# LED.net
KiCad netlist of a schematic drawn in Altium Designer
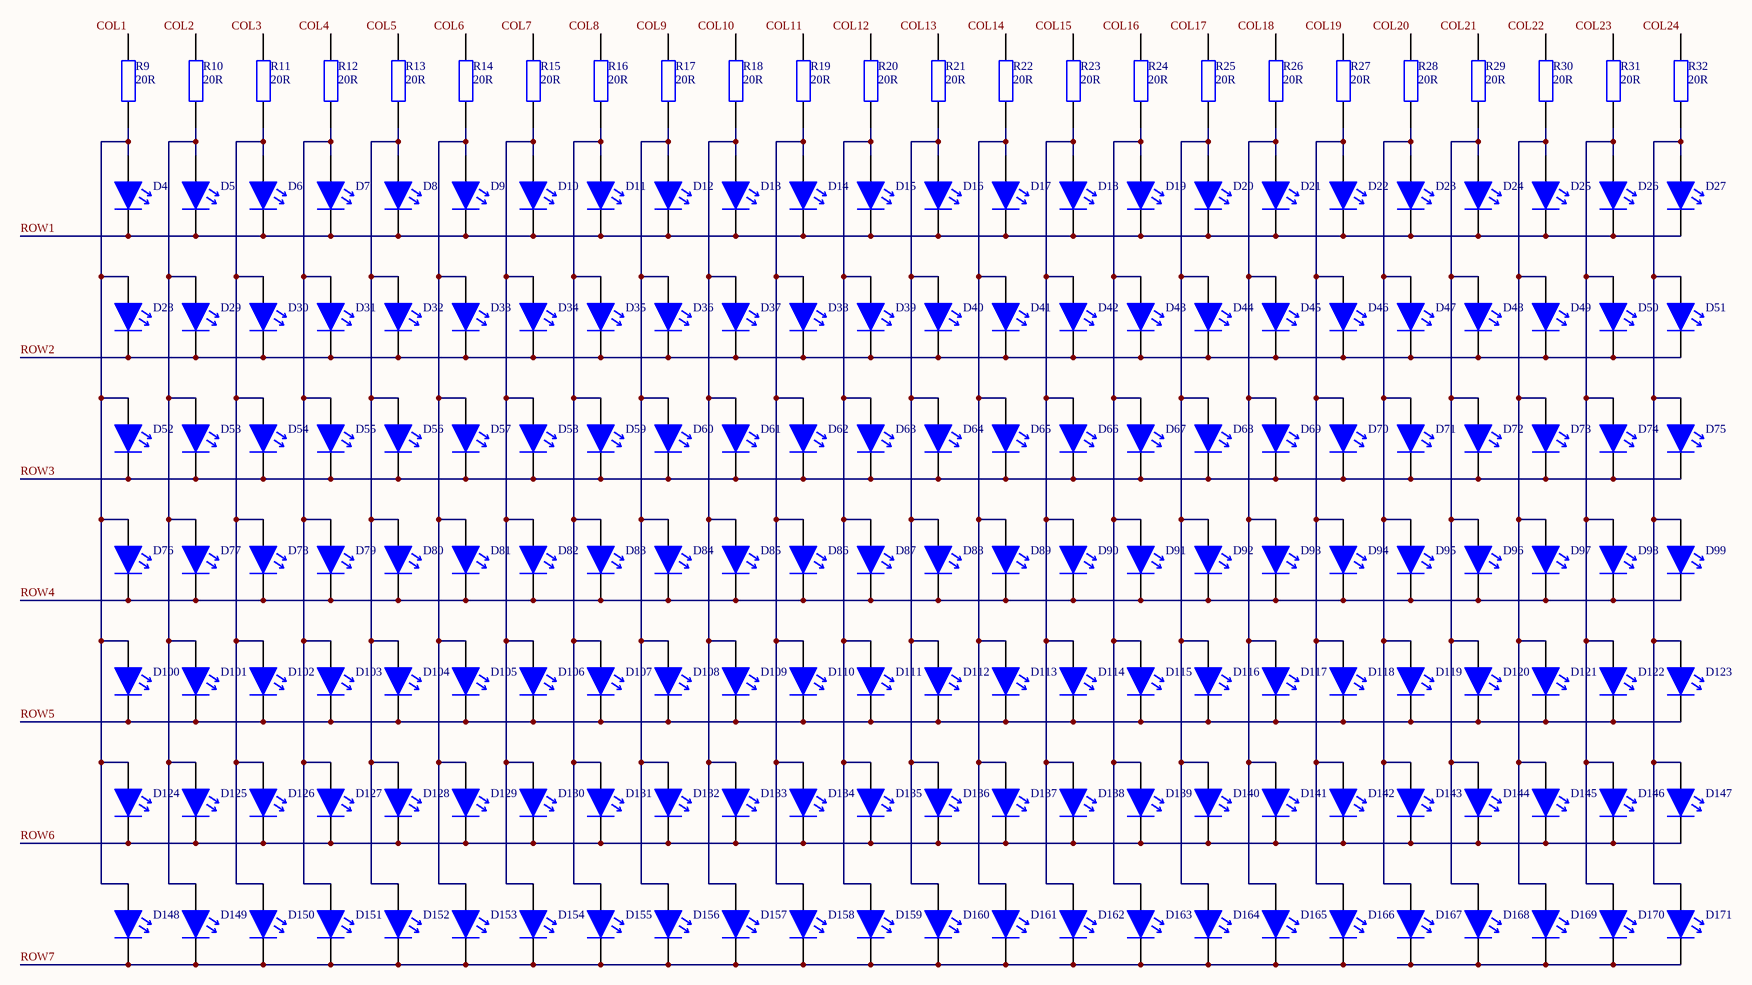
[diagram p0: LED.SchDoc]

(export (version "E")
  (design (tool "Eeschema 10.0.6"))
  (components
    (comp (ref "D4")
      (value "EAHE2835WD63")
      (footprint "LED_WHITE_1411_PLCC2")
      (description "LED Uni-Color White 39lm 6500K Chip LED 2-Pin PLCC T/R")
      (fields (field (name "MANUFACTURER") "Everlight") (field (name "DESIGNEDBY") "Aslı Kurt"))
      (libsource (lib "MyLibrary") (part "LED COOL WHITE 6500K 2PLCC 1411"))
    )
    (comp (ref "D5")
      (value "EAHE2835WD63")
      (footprint "LED_WHITE_1411_PLCC2")
      (description "LED Uni-Color White 39lm 6500K Chip LED 2-Pin PLCC T/R")
      (fields (field (name "MANUFACTURER") "Everlight") (field (name "DESIGNEDBY") "Aslı Kurt"))
      (libsource (lib "MyLibrary") (part "LED COOL WHITE 6500K 2PLCC 1411"))
    )
    (comp (ref "D6")
      (value "EAHE2835WD63")
      (footprint "LED_WHITE_1411_PLCC2")
      (description "LED Uni-Color White 39lm 6500K Chip LED 2-Pin PLCC T/R")
      (fields (field (name "MANUFACTURER") "Everlight") (field (name "DESIGNEDBY") "Aslı Kurt"))
      (libsource (lib "MyLibrary") (part "LED COOL WHITE 6500K 2PLCC 1411"))
    )
    (comp (ref "D7")
      (value "EAHE2835WD63")
      (footprint "LED_WHITE_1411_PLCC2")
      (description "LED Uni-Color White 39lm 6500K Chip LED 2-Pin PLCC T/R")
      (fields (field (name "MANUFACTURER") "Everlight") (field (name "DESIGNEDBY") "Aslı Kurt"))
      (libsource (lib "MyLibrary") (part "LED COOL WHITE 6500K 2PLCC 1411"))
    )
    (comp (ref "D8")
      (value "EAHE2835WD63")
      (footprint "LED_WHITE_1411_PLCC2")
      (description "LED Uni-Color White 39lm 6500K Chip LED 2-Pin PLCC T/R")
      (fields (field (name "MANUFACTURER") "Everlight") (field (name "DESIGNEDBY") "Aslı Kurt"))
      (libsource (lib "MyLibrary") (part "LED COOL WHITE 6500K 2PLCC 1411"))
    )
    (comp (ref "D9")
      (value "EAHE2835WD63")
      (footprint "LED_WHITE_1411_PLCC2")
      (description "LED Uni-Color White 39lm 6500K Chip LED 2-Pin PLCC T/R")
      (fields (field (name "MANUFACTURER") "Everlight") (field (name "DESIGNEDBY") "Aslı Kurt"))
      (libsource (lib "MyLibrary") (part "LED COOL WHITE 6500K 2PLCC 1411"))
    )
    (comp (ref "D10")
      (value "EAHE2835WD63")
      (footprint "LED_WHITE_1411_PLCC2")
      (description "LED Uni-Color White 39lm 6500K Chip LED 2-Pin PLCC T/R")
      (fields (field (name "MANUFACTURER") "Everlight") (field (name "DESIGNEDBY") "Aslı Kurt"))
      (libsource (lib "MyLibrary") (part "LED COOL WHITE 6500K 2PLCC 1411"))
    )
    (comp (ref "D11")
      (value "EAHE2835WD63")
      (footprint "LED_WHITE_1411_PLCC2")
      (description "LED Uni-Color White 39lm 6500K Chip LED 2-Pin PLCC T/R")
      (fields (field (name "MANUFACTURER") "Everlight") (field (name "DESIGNEDBY") "Aslı Kurt"))
      (libsource (lib "MyLibrary") (part "LED COOL WHITE 6500K 2PLCC 1411"))
    )
    (comp (ref "D12")
      (value "EAHE2835WD63")
      (footprint "LED_WHITE_1411_PLCC2")
      (description "LED Uni-Color White 39lm 6500K Chip LED 2-Pin PLCC T/R")
      (fields (field (name "MANUFACTURER") "Everlight") (field (name "DESIGNEDBY") "Aslı Kurt"))
      (libsource (lib "MyLibrary") (part "LED COOL WHITE 6500K 2PLCC 1411"))
    )
    (comp (ref "D13")
      (value "EAHE2835WD63")
      (footprint "LED_WHITE_1411_PLCC2")
      (description "LED Uni-Color White 39lm 6500K Chip LED 2-Pin PLCC T/R")
      (fields (field (name "MANUFACTURER") "Everlight") (field (name "DESIGNEDBY") "Aslı Kurt"))
      (libsource (lib "MyLibrary") (part "LED COOL WHITE 6500K 2PLCC 1411"))
    )
    (comp (ref "D14")
      (value "EAHE2835WD63")
      (footprint "LED_WHITE_1411_PLCC2")
      (description "LED Uni-Color White 39lm 6500K Chip LED 2-Pin PLCC T/R")
      (fields (field (name "MANUFACTURER") "Everlight") (field (name "DESIGNEDBY") "Aslı Kurt"))
      (libsource (lib "MyLibrary") (part "LED COOL WHITE 6500K 2PLCC 1411"))
    )
    (comp (ref "D15")
      (value "EAHE2835WD63")
      (footprint "LED_WHITE_1411_PLCC2")
      (description "LED Uni-Color White 39lm 6500K Chip LED 2-Pin PLCC T/R")
      (fields (field (name "MANUFACTURER") "Everlight") (field (name "DESIGNEDBY") "Aslı Kurt"))
      (libsource (lib "MyLibrary") (part "LED COOL WHITE 6500K 2PLCC 1411"))
    )
    (comp (ref "D16")
      (value "EAHE2835WD63")
      (footprint "LED_WHITE_1411_PLCC2")
      (description "LED Uni-Color White 39lm 6500K Chip LED 2-Pin PLCC T/R")
      (fields (field (name "MANUFACTURER") "Everlight") (field (name "DESIGNEDBY") "Aslı Kurt"))
      (libsource (lib "MyLibrary") (part "LED COOL WHITE 6500K 2PLCC 1411"))
    )
    (comp (ref "D17")
      (value "EAHE2835WD63")
      (footprint "LED_WHITE_1411_PLCC2")
      (description "LED Uni-Color White 39lm 6500K Chip LED 2-Pin PLCC T/R")
      (fields (field (name "MANUFACTURER") "Everlight") (field (name "DESIGNEDBY") "Aslı Kurt"))
      (libsource (lib "MyLibrary") (part "LED COOL WHITE 6500K 2PLCC 1411"))
    )
    (comp (ref "D18")
      (value "EAHE2835WD63")
      (footprint "LED_WHITE_1411_PLCC2")
      (description "LED Uni-Color White 39lm 6500K Chip LED 2-Pin PLCC T/R")
      (fields (field (name "MANUFACTURER") "Everlight") (field (name "DESIGNEDBY") "Aslı Kurt"))
      (libsource (lib "MyLibrary") (part "LED COOL WHITE 6500K 2PLCC 1411"))
    )
    (comp (ref "D19")
      (value "EAHE2835WD63")
      (footprint "LED_WHITE_1411_PLCC2")
      (description "LED Uni-Color White 39lm 6500K Chip LED 2-Pin PLCC T/R")
      (fields (field (name "MANUFACTURER") "Everlight") (field (name "DESIGNEDBY") "Aslı Kurt"))
      (libsource (lib "MyLibrary") (part "LED COOL WHITE 6500K 2PLCC 1411"))
    )
    (comp (ref "D20")
      (value "EAHE2835WD63")
      (footprint "LED_WHITE_1411_PLCC2")
      (description "LED Uni-Color White 39lm 6500K Chip LED 2-Pin PLCC T/R")
      (fields (field (name "MANUFACTURER") "Everlight") (field (name "DESIGNEDBY") "Aslı Kurt"))
      (libsource (lib "MyLibrary") (part "LED COOL WHITE 6500K 2PLCC 1411"))
    )
    (comp (ref "D21")
      (value "EAHE2835WD63")
      (footprint "LED_WHITE_1411_PLCC2")
      (description "LED Uni-Color White 39lm 6500K Chip LED 2-Pin PLCC T/R")
      (fields (field (name "MANUFACTURER") "Everlight") (field (name "DESIGNEDBY") "Aslı Kurt"))
      (libsource (lib "MyLibrary") (part "LED COOL WHITE 6500K 2PLCC 1411"))
    )
    (comp (ref "D22")
      (value "EAHE2835WD63")
      (footprint "LED_WHITE_1411_PLCC2")
      (description "LED Uni-Color White 39lm 6500K Chip LED 2-Pin PLCC T/R")
      (fields (field (name "MANUFACTURER") "Everlight") (field (name "DESIGNEDBY") "Aslı Kurt"))
      (libsource (lib "MyLibrary") (part "LED COOL WHITE 6500K 2PLCC 1411"))
    )
    (comp (ref "D23")
      (value "EAHE2835WD63")
      (footprint "LED_WHITE_1411_PLCC2")
      (description "LED Uni-Color White 39lm 6500K Chip LED 2-Pin PLCC T/R")
      (fields (field (name "MANUFACTURER") "Everlight") (field (name "DESIGNEDBY") "Aslı Kurt"))
      (libsource (lib "MyLibrary") (part "LED COOL WHITE 6500K 2PLCC 1411"))
    )
    (comp (ref "D24")
      (value "EAHE2835WD63")
      (footprint "LED_WHITE_1411_PLCC2")
      (description "LED Uni-Color White 39lm 6500K Chip LED 2-Pin PLCC T/R")
      (fields (field (name "MANUFACTURER") "Everlight") (field (name "DESIGNEDBY") "Aslı Kurt"))
      (libsource (lib "MyLibrary") (part "LED COOL WHITE 6500K 2PLCC 1411"))
    )
    (comp (ref "D25")
      (value "EAHE2835WD63")
      (footprint "LED_WHITE_1411_PLCC2")
      (description "LED Uni-Color White 39lm 6500K Chip LED 2-Pin PLCC T/R")
      (fields (field (name "MANUFACTURER") "Everlight") (field (name "DESIGNEDBY") "Aslı Kurt"))
      (libsource (lib "MyLibrary") (part "LED COOL WHITE 6500K 2PLCC 1411"))
    )
    (comp (ref "D26")
      (value "EAHE2835WD63")
      (footprint "LED_WHITE_1411_PLCC2")
      (description "LED Uni-Color White 39lm 6500K Chip LED 2-Pin PLCC T/R")
      (fields (field (name "MANUFACTURER") "Everlight") (field (name "DESIGNEDBY") "Aslı Kurt"))
      (libsource (lib "MyLibrary") (part "LED COOL WHITE 6500K 2PLCC 1411"))
    )
    (comp (ref "D27")
      (value "EAHE2835WD63")
      (footprint "LED_WHITE_1411_PLCC2")
      (description "LED Uni-Color White 39lm 6500K Chip LED 2-Pin PLCC T/R")
      (fields (field (name "MANUFACTURER") "Everlight") (field (name "DESIGNEDBY") "Aslı Kurt"))
      (libsource (lib "MyLibrary") (part "LED COOL WHITE 6500K 2PLCC 1411"))
    )
    (comp (ref "D28")
      (value "EAHE2835WD63")
      (footprint "LED_WHITE_1411_PLCC2")
      (description "LED Uni-Color White 39lm 6500K Chip LED 2-Pin PLCC T/R")
      (fields (field (name "MANUFACTURER") "Everlight") (field (name "DESIGNEDBY") "Aslı Kurt"))
      (libsource (lib "MyLibrary") (part "LED COOL WHITE 6500K 2PLCC 1411"))
    )
    (comp (ref "D29")
      (value "EAHE2835WD63")
      (footprint "LED_WHITE_1411_PLCC2")
      (description "LED Uni-Color White 39lm 6500K Chip LED 2-Pin PLCC T/R")
      (fields (field (name "MANUFACTURER") "Everlight") (field (name "DESIGNEDBY") "Aslı Kurt"))
      (libsource (lib "MyLibrary") (part "LED COOL WHITE 6500K 2PLCC 1411"))
    )
    (comp (ref "D30")
      (value "EAHE2835WD63")
      (footprint "LED_WHITE_1411_PLCC2")
      (description "LED Uni-Color White 39lm 6500K Chip LED 2-Pin PLCC T/R")
      (fields (field (name "MANUFACTURER") "Everlight") (field (name "DESIGNEDBY") "Aslı Kurt"))
      (libsource (lib "MyLibrary") (part "LED COOL WHITE 6500K 2PLCC 1411"))
    )
    (comp (ref "D31")
      (value "EAHE2835WD63")
      (footprint "LED_WHITE_1411_PLCC2")
      (description "LED Uni-Color White 39lm 6500K Chip LED 2-Pin PLCC T/R")
      (fields (field (name "MANUFACTURER") "Everlight") (field (name "DESIGNEDBY") "Aslı Kurt"))
      (libsource (lib "MyLibrary") (part "LED COOL WHITE 6500K 2PLCC 1411"))
    )
    (comp (ref "D32")
      (value "EAHE2835WD63")
      (footprint "LED_WHITE_1411_PLCC2")
      (description "LED Uni-Color White 39lm 6500K Chip LED 2-Pin PLCC T/R")
      (fields (field (name "MANUFACTURER") "Everlight") (field (name "DESIGNEDBY") "Aslı Kurt"))
      (libsource (lib "MyLibrary") (part "LED COOL WHITE 6500K 2PLCC 1411"))
    )
    (comp (ref "D33")
      (value "EAHE2835WD63")
      (footprint "LED_WHITE_1411_PLCC2")
      (description "LED Uni-Color White 39lm 6500K Chip LED 2-Pin PLCC T/R")
      (fields (field (name "MANUFACTURER") "Everlight") (field (name "DESIGNEDBY") "Aslı Kurt"))
      (libsource (lib "MyLibrary") (part "LED COOL WHITE 6500K 2PLCC 1411"))
    )
    (comp (ref "D34")
      (value "EAHE2835WD63")
      (footprint "LED_WHITE_1411_PLCC2")
      (description "LED Uni-Color White 39lm 6500K Chip LED 2-Pin PLCC T/R")
      (fields (field (name "MANUFACTURER") "Everlight") (field (name "DESIGNEDBY") "Aslı Kurt"))
      (libsource (lib "MyLibrary") (part "LED COOL WHITE 6500K 2PLCC 1411"))
    )
    (comp (ref "D35")
      (value "EAHE2835WD63")
      (footprint "LED_WHITE_1411_PLCC2")
      (description "LED Uni-Color White 39lm 6500K Chip LED 2-Pin PLCC T/R")
      (fields (field (name "MANUFACTURER") "Everlight") (field (name "DESIGNEDBY") "Aslı Kurt"))
      (libsource (lib "MyLibrary") (part "LED COOL WHITE 6500K 2PLCC 1411"))
    )
    (comp (ref "D36")
      (value "EAHE2835WD63")
      (footprint "LED_WHITE_1411_PLCC2")
      (description "LED Uni-Color White 39lm 6500K Chip LED 2-Pin PLCC T/R")
      (fields (field (name "MANUFACTURER") "Everlight") (field (name "DESIGNEDBY") "Aslı Kurt"))
      (libsource (lib "MyLibrary") (part "LED COOL WHITE 6500K 2PLCC 1411"))
    )
    (comp (ref "D37")
      (value "EAHE2835WD63")
      (footprint "LED_WHITE_1411_PLCC2")
      (description "LED Uni-Color White 39lm 6500K Chip LED 2-Pin PLCC T/R")
      (fields (field (name "MANUFACTURER") "Everlight") (field (name "DESIGNEDBY") "Aslı Kurt"))
      (libsource (lib "MyLibrary") (part "LED COOL WHITE 6500K 2PLCC 1411"))
    )
    (comp (ref "D38")
      (value "EAHE2835WD63")
      (footprint "LED_WHITE_1411_PLCC2")
      (description "LED Uni-Color White 39lm 6500K Chip LED 2-Pin PLCC T/R")
      (fields (field (name "MANUFACTURER") "Everlight") (field (name "DESIGNEDBY") "Aslı Kurt"))
      (libsource (lib "MyLibrary") (part "LED COOL WHITE 6500K 2PLCC 1411"))
    )
    (comp (ref "D39")
      (value "EAHE2835WD63")
      (footprint "LED_WHITE_1411_PLCC2")
      (description "LED Uni-Color White 39lm 6500K Chip LED 2-Pin PLCC T/R")
      (fields (field (name "MANUFACTURER") "Everlight") (field (name "DESIGNEDBY") "Aslı Kurt"))
      (libsource (lib "MyLibrary") (part "LED COOL WHITE 6500K 2PLCC 1411"))
    )
    (comp (ref "D40")
      (value "EAHE2835WD63")
      (footprint "LED_WHITE_1411_PLCC2")
      (description "LED Uni-Color White 39lm 6500K Chip LED 2-Pin PLCC T/R")
      (fields (field (name "MANUFACTURER") "Everlight") (field (name "DESIGNEDBY") "Aslı Kurt"))
      (libsource (lib "MyLibrary") (part "LED COOL WHITE 6500K 2PLCC 1411"))
    )
    (comp (ref "D41")
      (value "EAHE2835WD63")
      (footprint "LED_WHITE_1411_PLCC2")
      (description "LED Uni-Color White 39lm 6500K Chip LED 2-Pin PLCC T/R")
      (fields (field (name "MANUFACTURER") "Everlight") (field (name "DESIGNEDBY") "Aslı Kurt"))
      (libsource (lib "MyLibrary") (part "LED COOL WHITE 6500K 2PLCC 1411"))
    )
    (comp (ref "D42")
      (value "EAHE2835WD63")
      (footprint "LED_WHITE_1411_PLCC2")
      (description "LED Uni-Color White 39lm 6500K Chip LED 2-Pin PLCC T/R")
      (fields (field (name "MANUFACTURER") "Everlight") (field (name "DESIGNEDBY") "Aslı Kurt"))
      (libsource (lib "MyLibrary") (part "LED COOL WHITE 6500K 2PLCC 1411"))
    )
    (comp (ref "D43")
      (value "EAHE2835WD63")
      (footprint "LED_WHITE_1411_PLCC2")
      (description "LED Uni-Color White 39lm 6500K Chip LED 2-Pin PLCC T/R")
      (fields (field (name "MANUFACTURER") "Everlight") (field (name "DESIGNEDBY") "Aslı Kurt"))
      (libsource (lib "MyLibrary") (part "LED COOL WHITE 6500K 2PLCC 1411"))
    )
    (comp (ref "D44")
      (value "EAHE2835WD63")
      (footprint "LED_WHITE_1411_PLCC2")
      (description "LED Uni-Color White 39lm 6500K Chip LED 2-Pin PLCC T/R")
      (fields (field (name "MANUFACTURER") "Everlight") (field (name "DESIGNEDBY") "Aslı Kurt"))
      (libsource (lib "MyLibrary") (part "LED COOL WHITE 6500K 2PLCC 1411"))
    )
    (comp (ref "D45")
      (value "EAHE2835WD63")
      (footprint "LED_WHITE_1411_PLCC2")
      (description "LED Uni-Color White 39lm 6500K Chip LED 2-Pin PLCC T/R")
      (fields (field (name "MANUFACTURER") "Everlight") (field (name "DESIGNEDBY") "Aslı Kurt"))
      (libsource (lib "MyLibrary") (part "LED COOL WHITE 6500K 2PLCC 1411"))
    )
    (comp (ref "D46")
      (value "EAHE2835WD63")
      (footprint "LED_WHITE_1411_PLCC2")
      (description "LED Uni-Color White 39lm 6500K Chip LED 2-Pin PLCC T/R")
      (fields (field (name "MANUFACTURER") "Everlight") (field (name "DESIGNEDBY") "Aslı Kurt"))
      (libsource (lib "MyLibrary") (part "LED COOL WHITE 6500K 2PLCC 1411"))
    )
    (comp (ref "D47")
      (value "EAHE2835WD63")
      (footprint "LED_WHITE_1411_PLCC2")
      (description "LED Uni-Color White 39lm 6500K Chip LED 2-Pin PLCC T/R")
      (fields (field (name "MANUFACTURER") "Everlight") (field (name "DESIGNEDBY") "Aslı Kurt"))
      (libsource (lib "MyLibrary") (part "LED COOL WHITE 6500K 2PLCC 1411"))
    )
    (comp (ref "D48")
      (value "EAHE2835WD63")
      (footprint "LED_WHITE_1411_PLCC2")
      (description "LED Uni-Color White 39lm 6500K Chip LED 2-Pin PLCC T/R")
      (fields (field (name "MANUFACTURER") "Everlight") (field (name "DESIGNEDBY") "Aslı Kurt"))
      (libsource (lib "MyLibrary") (part "LED COOL WHITE 6500K 2PLCC 1411"))
    )
    (comp (ref "D49")
      (value "EAHE2835WD63")
      (footprint "LED_WHITE_1411_PLCC2")
      (description "LED Uni-Color White 39lm 6500K Chip LED 2-Pin PLCC T/R")
      (fields (field (name "MANUFACTURER") "Everlight") (field (name "DESIGNEDBY") "Aslı Kurt"))
      (libsource (lib "MyLibrary") (part "LED COOL WHITE 6500K 2PLCC 1411"))
    )
    (comp (ref "D50")
      (value "EAHE2835WD63")
      (footprint "LED_WHITE_1411_PLCC2")
      (description "LED Uni-Color White 39lm 6500K Chip LED 2-Pin PLCC T/R")
      (fields (field (name "MANUFACTURER") "Everlight") (field (name "DESIGNEDBY") "Aslı Kurt"))
      (libsource (lib "MyLibrary") (part "LED COOL WHITE 6500K 2PLCC 1411"))
    )
    (comp (ref "D51")
      (value "EAHE2835WD63")
      (footprint "LED_WHITE_1411_PLCC2")
      (description "LED Uni-Color White 39lm 6500K Chip LED 2-Pin PLCC T/R")
      (fields (field (name "MANUFACTURER") "Everlight") (field (name "DESIGNEDBY") "Aslı Kurt"))
      (libsource (lib "MyLibrary") (part "LED COOL WHITE 6500K 2PLCC 1411"))
    )
    (comp (ref "D52")
      (value "EAHE2835WD63")
      (footprint "LED_WHITE_1411_PLCC2")
      (description "LED Uni-Color White 39lm 6500K Chip LED 2-Pin PLCC T/R")
      (fields (field (name "MANUFACTURER") "Everlight") (field (name "DESIGNEDBY") "Aslı Kurt"))
      (libsource (lib "MyLibrary") (part "LED COOL WHITE 6500K 2PLCC 1411"))
    )
    (comp (ref "D53")
      (value "EAHE2835WD63")
      (footprint "LED_WHITE_1411_PLCC2")
      (description "LED Uni-Color White 39lm 6500K Chip LED 2-Pin PLCC T/R")
      (fields (field (name "MANUFACTURER") "Everlight") (field (name "DESIGNEDBY") "Aslı Kurt"))
      (libsource (lib "MyLibrary") (part "LED COOL WHITE 6500K 2PLCC 1411"))
    )
    (comp (ref "D54")
      (value "EAHE2835WD63")
      (footprint "LED_WHITE_1411_PLCC2")
      (description "LED Uni-Color White 39lm 6500K Chip LED 2-Pin PLCC T/R")
      (fields (field (name "MANUFACTURER") "Everlight") (field (name "DESIGNEDBY") "Aslı Kurt"))
      (libsource (lib "MyLibrary") (part "LED COOL WHITE 6500K 2PLCC 1411"))
    )
    (comp (ref "D55")
      (value "EAHE2835WD63")
      (footprint "LED_WHITE_1411_PLCC2")
      (description "LED Uni-Color White 39lm 6500K Chip LED 2-Pin PLCC T/R")
      (fields (field (name "MANUFACTURER") "Everlight") (field (name "DESIGNEDBY") "Aslı Kurt"))
      (libsource (lib "MyLibrary") (part "LED COOL WHITE 6500K 2PLCC 1411"))
    )
    (comp (ref "D56")
      (value "EAHE2835WD63")
      (footprint "LED_WHITE_1411_PLCC2")
      (description "LED Uni-Color White 39lm 6500K Chip LED 2-Pin PLCC T/R")
      (fields (field (name "MANUFACTURER") "Everlight") (field (name "DESIGNEDBY") "Aslı Kurt"))
      (libsource (lib "MyLibrary") (part "LED COOL WHITE 6500K 2PLCC 1411"))
    )
    (comp (ref "D57")
      (value "EAHE2835WD63")
      (footprint "LED_WHITE_1411_PLCC2")
      (description "LED Uni-Color White 39lm 6500K Chip LED 2-Pin PLCC T/R")
      (fields (field (name "MANUFACTURER") "Everlight") (field (name "DESIGNEDBY") "Aslı Kurt"))
      (libsource (lib "MyLibrary") (part "LED COOL WHITE 6500K 2PLCC 1411"))
    )
    (comp (ref "D58")
      (value "EAHE2835WD63")
      (footprint "LED_WHITE_1411_PLCC2")
      (description "LED Uni-Color White 39lm 6500K Chip LED 2-Pin PLCC T/R")
      (fields (field (name "MANUFACTURER") "Everlight") (field (name "DESIGNEDBY") "Aslı Kurt"))
      (libsource (lib "MyLibrary") (part "LED COOL WHITE 6500K 2PLCC 1411"))
    )
    (comp (ref "D59")
      (value "EAHE2835WD63")
      (footprint "LED_WHITE_1411_PLCC2")
      (description "LED Uni-Color White 39lm 6500K Chip LED 2-Pin PLCC T/R")
      (fields (field (name "MANUFACTURER") "Everlight") (field (name "DESIGNEDBY") "Aslı Kurt"))
      (libsource (lib "MyLibrary") (part "LED COOL WHITE 6500K 2PLCC 1411"))
    )
    (comp (ref "D60")
      (value "EAHE2835WD63")
      (footprint "LED_WHITE_1411_PLCC2")
      (description "LED Uni-Color White 39lm 6500K Chip LED 2-Pin PLCC T/R")
      (fields (field (name "MANUFACTURER") "Everlight") (field (name "DESIGNEDBY") "Aslı Kurt"))
      (libsource (lib "MyLibrary") (part "LED COOL WHITE 6500K 2PLCC 1411"))
    )
    (comp (ref "D61")
      (value "EAHE2835WD63")
      (footprint "LED_WHITE_1411_PLCC2")
      (description "LED Uni-Color White 39lm 6500K Chip LED 2-Pin PLCC T/R")
      (fields (field (name "MANUFACTURER") "Everlight") (field (name "DESIGNEDBY") "Aslı Kurt"))
      (libsource (lib "MyLibrary") (part "LED COOL WHITE 6500K 2PLCC 1411"))
    )
    (comp (ref "D62")
      (value "EAHE2835WD63")
      (footprint "LED_WHITE_1411_PLCC2")
      (description "LED Uni-Color White 39lm 6500K Chip LED 2-Pin PLCC T/R")
      (fields (field (name "MANUFACTURER") "Everlight") (field (name "DESIGNEDBY") "Aslı Kurt"))
      (libsource (lib "MyLibrary") (part "LED COOL WHITE 6500K 2PLCC 1411"))
    )
    (comp (ref "D63")
      (value "EAHE2835WD63")
      (footprint "LED_WHITE_1411_PLCC2")
      (description "LED Uni-Color White 39lm 6500K Chip LED 2-Pin PLCC T/R")
      (fields (field (name "MANUFACTURER") "Everlight") (field (name "DESIGNEDBY") "Aslı Kurt"))
      (libsource (lib "MyLibrary") (part "LED COOL WHITE 6500K 2PLCC 1411"))
    )
    (comp (ref "D64")
      (value "EAHE2835WD63")
      (footprint "LED_WHITE_1411_PLCC2")
      (description "LED Uni-Color White 39lm 6500K Chip LED 2-Pin PLCC T/R")
      (fields (field (name "MANUFACTURER") "Everlight") (field (name "DESIGNEDBY") "Aslı Kurt"))
      (libsource (lib "MyLibrary") (part "LED COOL WHITE 6500K 2PLCC 1411"))
    )
    (comp (ref "D65")
      (value "EAHE2835WD63")
      (footprint "LED_WHITE_1411_PLCC2")
      (description "LED Uni-Color White 39lm 6500K Chip LED 2-Pin PLCC T/R")
      (fields (field (name "MANUFACTURER") "Everlight") (field (name "DESIGNEDBY") "Aslı Kurt"))
      (libsource (lib "MyLibrary") (part "LED COOL WHITE 6500K 2PLCC 1411"))
    )
    (comp (ref "D66")
      (value "EAHE2835WD63")
      (footprint "LED_WHITE_1411_PLCC2")
      (description "LED Uni-Color White 39lm 6500K Chip LED 2-Pin PLCC T/R")
      (fields (field (name "MANUFACTURER") "Everlight") (field (name "DESIGNEDBY") "Aslı Kurt"))
      (libsource (lib "MyLibrary") (part "LED COOL WHITE 6500K 2PLCC 1411"))
    )
    (comp (ref "D67")
      (value "EAHE2835WD63")
      (footprint "LED_WHITE_1411_PLCC2")
      (description "LED Uni-Color White 39lm 6500K Chip LED 2-Pin PLCC T/R")
      (fields (field (name "MANUFACTURER") "Everlight") (field (name "DESIGNEDBY") "Aslı Kurt"))
      (libsource (lib "MyLibrary") (part "LED COOL WHITE 6500K 2PLCC 1411"))
    )
    (comp (ref "D68")
      (value "EAHE2835WD63")
      (footprint "LED_WHITE_1411_PLCC2")
      (description "LED Uni-Color White 39lm 6500K Chip LED 2-Pin PLCC T/R")
      (fields (field (name "MANUFACTURER") "Everlight") (field (name "DESIGNEDBY") "Aslı Kurt"))
      (libsource (lib "MyLibrary") (part "LED COOL WHITE 6500K 2PLCC 1411"))
    )
    (comp (ref "D69")
      (value "EAHE2835WD63")
      (footprint "LED_WHITE_1411_PLCC2")
      (description "LED Uni-Color White 39lm 6500K Chip LED 2-Pin PLCC T/R")
      (fields (field (name "MANUFACTURER") "Everlight") (field (name "DESIGNEDBY") "Aslı Kurt"))
      (libsource (lib "MyLibrary") (part "LED COOL WHITE 6500K 2PLCC 1411"))
    )
    (comp (ref "D70")
      (value "EAHE2835WD63")
      (footprint "LED_WHITE_1411_PLCC2")
      (description "LED Uni-Color White 39lm 6500K Chip LED 2-Pin PLCC T/R")
      (fields (field (name "MANUFACTURER") "Everlight") (field (name "DESIGNEDBY") "Aslı Kurt"))
      (libsource (lib "MyLibrary") (part "LED COOL WHITE 6500K 2PLCC 1411"))
    )
    (comp (ref "D71")
      (value "EAHE2835WD63")
      (footprint "LED_WHITE_1411_PLCC2")
      (description "LED Uni-Color White 39lm 6500K Chip LED 2-Pin PLCC T/R")
      (fields (field (name "MANUFACTURER") "Everlight") (field (name "DESIGNEDBY") "Aslı Kurt"))
      (libsource (lib "MyLibrary") (part "LED COOL WHITE 6500K 2PLCC 1411"))
    )
    (comp (ref "D72")
      (value "EAHE2835WD63")
      (footprint "LED_WHITE_1411_PLCC2")
      (description "LED Uni-Color White 39lm 6500K Chip LED 2-Pin PLCC T/R")
      (fields (field (name "MANUFACTURER") "Everlight") (field (name "DESIGNEDBY") "Aslı Kurt"))
      (libsource (lib "MyLibrary") (part "LED COOL WHITE 6500K 2PLCC 1411"))
    )
    (comp (ref "D73")
      (value "EAHE2835WD63")
      (footprint "LED_WHITE_1411_PLCC2")
      (description "LED Uni-Color White 39lm 6500K Chip LED 2-Pin PLCC T/R")
      (fields (field (name "MANUFACTURER") "Everlight") (field (name "DESIGNEDBY") "Aslı Kurt"))
      (libsource (lib "MyLibrary") (part "LED COOL WHITE 6500K 2PLCC 1411"))
    )
    (comp (ref "D74")
      (value "EAHE2835WD63")
      (footprint "LED_WHITE_1411_PLCC2")
      (description "LED Uni-Color White 39lm 6500K Chip LED 2-Pin PLCC T/R")
      (fields (field (name "MANUFACTURER") "Everlight") (field (name "DESIGNEDBY") "Aslı Kurt"))
      (libsource (lib "MyLibrary") (part "LED COOL WHITE 6500K 2PLCC 1411"))
    )
    (comp (ref "D75")
      (value "EAHE2835WD63")
      (footprint "LED_WHITE_1411_PLCC2")
      (description "LED Uni-Color White 39lm 6500K Chip LED 2-Pin PLCC T/R")
      (fields (field (name "MANUFACTURER") "Everlight") (field (name "DESIGNEDBY") "Aslı Kurt"))
      (libsource (lib "MyLibrary") (part "LED COOL WHITE 6500K 2PLCC 1411"))
    )
    (comp (ref "D76")
      (value "EAHE2835WD63")
      (footprint "LED_WHITE_1411_PLCC2")
      (description "LED Uni-Color White 39lm 6500K Chip LED 2-Pin PLCC T/R")
      (fields (field (name "MANUFACTURER") "Everlight") (field (name "DESIGNEDBY") "Aslı Kurt"))
      (libsource (lib "MyLibrary") (part "LED COOL WHITE 6500K 2PLCC 1411"))
    )
    (comp (ref "D77")
      (value "EAHE2835WD63")
      (footprint "LED_WHITE_1411_PLCC2")
      (description "LED Uni-Color White 39lm 6500K Chip LED 2-Pin PLCC T/R")
      (fields (field (name "MANUFACTURER") "Everlight") (field (name "DESIGNEDBY") "Aslı Kurt"))
      (libsource (lib "MyLibrary") (part "LED COOL WHITE 6500K 2PLCC 1411"))
    )
    (comp (ref "D78")
      (value "EAHE2835WD63")
      (footprint "LED_WHITE_1411_PLCC2")
      (description "LED Uni-Color White 39lm 6500K Chip LED 2-Pin PLCC T/R")
      (fields (field (name "MANUFACTURER") "Everlight") (field (name "DESIGNEDBY") "Aslı Kurt"))
      (libsource (lib "MyLibrary") (part "LED COOL WHITE 6500K 2PLCC 1411"))
    )
    (comp (ref "D79")
      (value "EAHE2835WD63")
      (footprint "LED_WHITE_1411_PLCC2")
      (description "LED Uni-Color White 39lm 6500K Chip LED 2-Pin PLCC T/R")
      (fields (field (name "MANUFACTURER") "Everlight") (field (name "DESIGNEDBY") "Aslı Kurt"))
      (libsource (lib "MyLibrary") (part "LED COOL WHITE 6500K 2PLCC 1411"))
    )
    (comp (ref "D80")
      (value "EAHE2835WD63")
      (footprint "LED_WHITE_1411_PLCC2")
      (description "LED Uni-Color White 39lm 6500K Chip LED 2-Pin PLCC T/R")
      (fields (field (name "MANUFACTURER") "Everlight") (field (name "DESIGNEDBY") "Aslı Kurt"))
      (libsource (lib "MyLibrary") (part "LED COOL WHITE 6500K 2PLCC 1411"))
    )
    (comp (ref "D81")
      (value "EAHE2835WD63")
      (footprint "LED_WHITE_1411_PLCC2")
      (description "LED Uni-Color White 39lm 6500K Chip LED 2-Pin PLCC T/R")
      (fields (field (name "MANUFACTURER") "Everlight") (field (name "DESIGNEDBY") "Aslı Kurt"))
      (libsource (lib "MyLibrary") (part "LED COOL WHITE 6500K 2PLCC 1411"))
    )
    (comp (ref "D82")
      (value "EAHE2835WD63")
      (footprint "LED_WHITE_1411_PLCC2")
      (description "LED Uni-Color White 39lm 6500K Chip LED 2-Pin PLCC T/R")
      (fields (field (name "MANUFACTURER") "Everlight") (field (name "DESIGNEDBY") "Aslı Kurt"))
      (libsource (lib "MyLibrary") (part "LED COOL WHITE 6500K 2PLCC 1411"))
    )
    (comp (ref "D83")
      (value "EAHE2835WD63")
      (footprint "LED_WHITE_1411_PLCC2")
      (description "LED Uni-Color White 39lm 6500K Chip LED 2-Pin PLCC T/R")
      (fields (field (name "MANUFACTURER") "Everlight") (field (name "DESIGNEDBY") "Aslı Kurt"))
      (libsource (lib "MyLibrary") (part "LED COOL WHITE 6500K 2PLCC 1411"))
    )
    (comp (ref "D84")
      (value "EAHE2835WD63")
      (footprint "LED_WHITE_1411_PLCC2")
      (description "LED Uni-Color White 39lm 6500K Chip LED 2-Pin PLCC T/R")
      (fields (field (name "MANUFACTURER") "Everlight") (field (name "DESIGNEDBY") "Aslı Kurt"))
      (libsource (lib "MyLibrary") (part "LED COOL WHITE 6500K 2PLCC 1411"))
    )
    (comp (ref "D85")
      (value "EAHE2835WD63")
      (footprint "LED_WHITE_1411_PLCC2")
      (description "LED Uni-Color White 39lm 6500K Chip LED 2-Pin PLCC T/R")
      (fields (field (name "MANUFACTURER") "Everlight") (field (name "DESIGNEDBY") "Aslı Kurt"))
      (libsource (lib "MyLibrary") (part "LED COOL WHITE 6500K 2PLCC 1411"))
    )
    (comp (ref "D86")
      (value "EAHE2835WD63")
      (footprint "LED_WHITE_1411_PLCC2")
      (description "LED Uni-Color White 39lm 6500K Chip LED 2-Pin PLCC T/R")
      (fields (field (name "MANUFACTURER") "Everlight") (field (name "DESIGNEDBY") "Aslı Kurt"))
      (libsource (lib "MyLibrary") (part "LED COOL WHITE 6500K 2PLCC 1411"))
    )
    (comp (ref "D87")
      (value "EAHE2835WD63")
      (footprint "LED_WHITE_1411_PLCC2")
      (description "LED Uni-Color White 39lm 6500K Chip LED 2-Pin PLCC T/R")
      (fields (field (name "MANUFACTURER") "Everlight") (field (name "DESIGNEDBY") "Aslı Kurt"))
      (libsource (lib "MyLibrary") (part "LED COOL WHITE 6500K 2PLCC 1411"))
    )
    (comp (ref "D88")
      (value "EAHE2835WD63")
      (footprint "LED_WHITE_1411_PLCC2")
      (description "LED Uni-Color White 39lm 6500K Chip LED 2-Pin PLCC T/R")
      (fields (field (name "MANUFACTURER") "Everlight") (field (name "DESIGNEDBY") "Aslı Kurt"))
      (libsource (lib "MyLibrary") (part "LED COOL WHITE 6500K 2PLCC 1411"))
    )
    (comp (ref "D89")
      (value "EAHE2835WD63")
      (footprint "LED_WHITE_1411_PLCC2")
      (description "LED Uni-Color White 39lm 6500K Chip LED 2-Pin PLCC T/R")
      (fields (field (name "MANUFACTURER") "Everlight") (field (name "DESIGNEDBY") "Aslı Kurt"))
      (libsource (lib "MyLibrary") (part "LED COOL WHITE 6500K 2PLCC 1411"))
    )
    (comp (ref "D90")
      (value "EAHE2835WD63")
      (footprint "LED_WHITE_1411_PLCC2")
      (description "LED Uni-Color White 39lm 6500K Chip LED 2-Pin PLCC T/R")
      (fields (field (name "MANUFACTURER") "Everlight") (field (name "DESIGNEDBY") "Aslı Kurt"))
      (libsource (lib "MyLibrary") (part "LED COOL WHITE 6500K 2PLCC 1411"))
    )
    (comp (ref "D91")
      (value "EAHE2835WD63")
      (footprint "LED_WHITE_1411_PLCC2")
      (description "LED Uni-Color White 39lm 6500K Chip LED 2-Pin PLCC T/R")
      (fields (field (name "MANUFACTURER") "Everlight") (field (name "DESIGNEDBY") "Aslı Kurt"))
      (libsource (lib "MyLibrary") (part "LED COOL WHITE 6500K 2PLCC 1411"))
    )
    (comp (ref "D92")
      (value "EAHE2835WD63")
      (footprint "LED_WHITE_1411_PLCC2")
      (description "LED Uni-Color White 39lm 6500K Chip LED 2-Pin PLCC T/R")
      (fields (field (name "MANUFACTURER") "Everlight") (field (name "DESIGNEDBY") "Aslı Kurt"))
      (libsource (lib "MyLibrary") (part "LED COOL WHITE 6500K 2PLCC 1411"))
    )
    (comp (ref "D93")
      (value "EAHE2835WD63")
      (footprint "LED_WHITE_1411_PLCC2")
      (description "LED Uni-Color White 39lm 6500K Chip LED 2-Pin PLCC T/R")
      (fields (field (name "MANUFACTURER") "Everlight") (field (name "DESIGNEDBY") "Aslı Kurt"))
      (libsource (lib "MyLibrary") (part "LED COOL WHITE 6500K 2PLCC 1411"))
    )
    (comp (ref "D94")
      (value "EAHE2835WD63")
      (footprint "LED_WHITE_1411_PLCC2")
      (description "LED Uni-Color White 39lm 6500K Chip LED 2-Pin PLCC T/R")
      (fields (field (name "MANUFACTURER") "Everlight") (field (name "DESIGNEDBY") "Aslı Kurt"))
      (libsource (lib "MyLibrary") (part "LED COOL WHITE 6500K 2PLCC 1411"))
    )
    (comp (ref "D95")
      (value "EAHE2835WD63")
      (footprint "LED_WHITE_1411_PLCC2")
      (description "LED Uni-Color White 39lm 6500K Chip LED 2-Pin PLCC T/R")
      (fields (field (name "MANUFACTURER") "Everlight") (field (name "DESIGNEDBY") "Aslı Kurt"))
      (libsource (lib "MyLibrary") (part "LED COOL WHITE 6500K 2PLCC 1411"))
    )
    (comp (ref "D96")
      (value "EAHE2835WD63")
      (footprint "LED_WHITE_1411_PLCC2")
      (description "LED Uni-Color White 39lm 6500K Chip LED 2-Pin PLCC T/R")
      (fields (field (name "MANUFACTURER") "Everlight") (field (name "DESIGNEDBY") "Aslı Kurt"))
      (libsource (lib "MyLibrary") (part "LED COOL WHITE 6500K 2PLCC 1411"))
    )
    (comp (ref "D97")
      (value "EAHE2835WD63")
      (footprint "LED_WHITE_1411_PLCC2")
      (description "LED Uni-Color White 39lm 6500K Chip LED 2-Pin PLCC T/R")
      (fields (field (name "MANUFACTURER") "Everlight") (field (name "DESIGNEDBY") "Aslı Kurt"))
      (libsource (lib "MyLibrary") (part "LED COOL WHITE 6500K 2PLCC 1411"))
    )
    (comp (ref "D98")
      (value "EAHE2835WD63")
      (footprint "LED_WHITE_1411_PLCC2")
      (description "LED Uni-Color White 39lm 6500K Chip LED 2-Pin PLCC T/R")
      (fields (field (name "MANUFACTURER") "Everlight") (field (name "DESIGNEDBY") "Aslı Kurt"))
      (libsource (lib "MyLibrary") (part "LED COOL WHITE 6500K 2PLCC 1411"))
    )
    (comp (ref "D99")
      (value "EAHE2835WD63")
      (footprint "LED_WHITE_1411_PLCC2")
      (description "LED Uni-Color White 39lm 6500K Chip LED 2-Pin PLCC T/R")
      (fields (field (name "MANUFACTURER") "Everlight") (field (name "DESIGNEDBY") "Aslı Kurt"))
      (libsource (lib "MyLibrary") (part "LED COOL WHITE 6500K 2PLCC 1411"))
    )
    (comp (ref "D100")
      (value "EAHE2835WD63")
      (footprint "LED_WHITE_1411_PLCC2")
      (description "LED Uni-Color White 39lm 6500K Chip LED 2-Pin PLCC T/R")
      (fields (field (name "MANUFACTURER") "Everlight") (field (name "DESIGNEDBY") "Aslı Kurt"))
      (libsource (lib "MyLibrary") (part "LED COOL WHITE 6500K 2PLCC 1411"))
    )
    (comp (ref "D101")
      (value "EAHE2835WD63")
      (footprint "LED_WHITE_1411_PLCC2")
      (description "LED Uni-Color White 39lm 6500K Chip LED 2-Pin PLCC T/R")
      (fields (field (name "MANUFACTURER") "Everlight") (field (name "DESIGNEDBY") "Aslı Kurt"))
      (libsource (lib "MyLibrary") (part "LED COOL WHITE 6500K 2PLCC 1411"))
    )
    (comp (ref "D102")
      (value "EAHE2835WD63")
      (footprint "LED_WHITE_1411_PLCC2")
      (description "LED Uni-Color White 39lm 6500K Chip LED 2-Pin PLCC T/R")
      (fields (field (name "MANUFACTURER") "Everlight") (field (name "DESIGNEDBY") "Aslı Kurt"))
      (libsource (lib "MyLibrary") (part "LED COOL WHITE 6500K 2PLCC 1411"))
    )
    (comp (ref "D103")
      (value "EAHE2835WD63")
      (footprint "LED_WHITE_1411_PLCC2")
      (description "LED Uni-Color White 39lm 6500K Chip LED 2-Pin PLCC T/R")
      (fields (field (name "MANUFACTURER") "Everlight") (field (name "DESIGNEDBY") "Aslı Kurt"))
      (libsource (lib "MyLibrary") (part "LED COOL WHITE 6500K 2PLCC 1411"))
    )
    (comp (ref "D104")
      (value "EAHE2835WD63")
      (footprint "LED_WHITE_1411_PLCC2")
      (description "LED Uni-Color White 39lm 6500K Chip LED 2-Pin PLCC T/R")
      (fields (field (name "MANUFACTURER") "Everlight") (field (name "DESIGNEDBY") "Aslı Kurt"))
      (libsource (lib "MyLibrary") (part "LED COOL WHITE 6500K 2PLCC 1411"))
    )
    (comp (ref "D105")
      (value "EAHE2835WD63")
      (footprint "LED_WHITE_1411_PLCC2")
      (description "LED Uni-Color White 39lm 6500K Chip LED 2-Pin PLCC T/R")
      (fields (field (name "MANUFACTURER") "Everlight") (field (name "DESIGNEDBY") "Aslı Kurt"))
      (libsource (lib "MyLibrary") (part "LED COOL WHITE 6500K 2PLCC 1411"))
    )
    (comp (ref "D106")
      (value "EAHE2835WD63")
      (footprint "LED_WHITE_1411_PLCC2")
      (description "LED Uni-Color White 39lm 6500K Chip LED 2-Pin PLCC T/R")
      (fields (field (name "MANUFACTURER") "Everlight") (field (name "DESIGNEDBY") "Aslı Kurt"))
      (libsource (lib "MyLibrary") (part "LED COOL WHITE 6500K 2PLCC 1411"))
    )
    (comp (ref "D107")
      (value "EAHE2835WD63")
      (footprint "LED_WHITE_1411_PLCC2")
      (description "LED Uni-Color White 39lm 6500K Chip LED 2-Pin PLCC T/R")
      (fields (field (name "MANUFACTURER") "Everlight") (field (name "DESIGNEDBY") "Aslı Kurt"))
      (libsource (lib "MyLibrary") (part "LED COOL WHITE 6500K 2PLCC 1411"))
    )
    (comp (ref "D108")
      (value "EAHE2835WD63")
      (footprint "LED_WHITE_1411_PLCC2")
      (description "LED Uni-Color White 39lm 6500K Chip LED 2-Pin PLCC T/R")
      (fields (field (name "MANUFACTURER") "Everlight") (field (name "DESIGNEDBY") "Aslı Kurt"))
      (libsource (lib "MyLibrary") (part "LED COOL WHITE 6500K 2PLCC 1411"))
    )
    (comp (ref "D109")
      (value "EAHE2835WD63")
      (footprint "LED_WHITE_1411_PLCC2")
      (description "LED Uni-Color White 39lm 6500K Chip LED 2-Pin PLCC T/R")
      (fields (field (name "MANUFACTURER") "Everlight") (field (name "DESIGNEDBY") "Aslı Kurt"))
      (libsource (lib "MyLibrary") (part "LED COOL WHITE 6500K 2PLCC 1411"))
    )
    (comp (ref "D110")
      (value "EAHE2835WD63")
      (footprint "LED_WHITE_1411_PLCC2")
      (description "LED Uni-Color White 39lm 6500K Chip LED 2-Pin PLCC T/R")
      (fields (field (name "MANUFACTURER") "Everlight") (field (name "DESIGNEDBY") "Aslı Kurt"))
      (libsource (lib "MyLibrary") (part "LED COOL WHITE 6500K 2PLCC 1411"))
    )
    (comp (ref "D111")
      (value "EAHE2835WD63")
      (footprint "LED_WHITE_1411_PLCC2")
      (description "LED Uni-Color White 39lm 6500K Chip LED 2-Pin PLCC T/R")
      (fields (field (name "MANUFACTURER") "Everlight") (field (name "DESIGNEDBY") "Aslı Kurt"))
      (libsource (lib "MyLibrary") (part "LED COOL WHITE 6500K 2PLCC 1411"))
    )
    (comp (ref "D112")
      (value "EAHE2835WD63")
      (footprint "LED_WHITE_1411_PLCC2")
      (description "LED Uni-Color White 39lm 6500K Chip LED 2-Pin PLCC T/R")
      (fields (field (name "MANUFACTURER") "Everlight") (field (name "DESIGNEDBY") "Aslı Kurt"))
      (libsource (lib "MyLibrary") (part "LED COOL WHITE 6500K 2PLCC 1411"))
    )
    (comp (ref "D113")
      (value "EAHE2835WD63")
      (footprint "LED_WHITE_1411_PLCC2")
      (description "LED Uni-Color White 39lm 6500K Chip LED 2-Pin PLCC T/R")
      (fields (field (name "MANUFACTURER") "Everlight") (field (name "DESIGNEDBY") "Aslı Kurt"))
      (libsource (lib "MyLibrary") (part "LED COOL WHITE 6500K 2PLCC 1411"))
    )
    (comp (ref "D114")
      (value "EAHE2835WD63")
      (footprint "LED_WHITE_1411_PLCC2")
      (description "LED Uni-Color White 39lm 6500K Chip LED 2-Pin PLCC T/R")
      (fields (field (name "MANUFACTURER") "Everlight") (field (name "DESIGNEDBY") "Aslı Kurt"))
      (libsource (lib "MyLibrary") (part "LED COOL WHITE 6500K 2PLCC 1411"))
    )
    (comp (ref "D115")
      (value "EAHE2835WD63")
      (footprint "LED_WHITE_1411_PLCC2")
      (description "LED Uni-Color White 39lm 6500K Chip LED 2-Pin PLCC T/R")
      (fields (field (name "MANUFACTURER") "Everlight") (field (name "DESIGNEDBY") "Aslı Kurt"))
      (libsource (lib "MyLibrary") (part "LED COOL WHITE 6500K 2PLCC 1411"))
    )
    (comp (ref "D116")
      (value "EAHE2835WD63")
      (footprint "LED_WHITE_1411_PLCC2")
      (description "LED Uni-Color White 39lm 6500K Chip LED 2-Pin PLCC T/R")
      (fields (field (name "MANUFACTURER") "Everlight") (field (name "DESIGNEDBY") "Aslı Kurt"))
      (libsource (lib "MyLibrary") (part "LED COOL WHITE 6500K 2PLCC 1411"))
    )
    (comp (ref "D117")
      (value "EAHE2835WD63")
      (footprint "LED_WHITE_1411_PLCC2")
      (description "LED Uni-Color White 39lm 6500K Chip LED 2-Pin PLCC T/R")
      (fields (field (name "MANUFACTURER") "Everlight") (field (name "DESIGNEDBY") "Aslı Kurt"))
      (libsource (lib "MyLibrary") (part "LED COOL WHITE 6500K 2PLCC 1411"))
    )
    (comp (ref "D118")
      (value "EAHE2835WD63")
      (footprint "LED_WHITE_1411_PLCC2")
      (description "LED Uni-Color White 39lm 6500K Chip LED 2-Pin PLCC T/R")
      (fields (field (name "MANUFACTURER") "Everlight") (field (name "DESIGNEDBY") "Aslı Kurt"))
      (libsource (lib "MyLibrary") (part "LED COOL WHITE 6500K 2PLCC 1411"))
    )
    (comp (ref "D119")
      (value "EAHE2835WD63")
      (footprint "LED_WHITE_1411_PLCC2")
      (description "LED Uni-Color White 39lm 6500K Chip LED 2-Pin PLCC T/R")
      (fields (field (name "MANUFACTURER") "Everlight") (field (name "DESIGNEDBY") "Aslı Kurt"))
      (libsource (lib "MyLibrary") (part "LED COOL WHITE 6500K 2PLCC 1411"))
    )
    (comp (ref "D120")
      (value "EAHE2835WD63")
      (footprint "LED_WHITE_1411_PLCC2")
      (description "LED Uni-Color White 39lm 6500K Chip LED 2-Pin PLCC T/R")
      (fields (field (name "MANUFACTURER") "Everlight") (field (name "DESIGNEDBY") "Aslı Kurt"))
      (libsource (lib "MyLibrary") (part "LED COOL WHITE 6500K 2PLCC 1411"))
    )
    (comp (ref "D121")
      (value "EAHE2835WD63")
      (footprint "LED_WHITE_1411_PLCC2")
      (description "LED Uni-Color White 39lm 6500K Chip LED 2-Pin PLCC T/R")
      (fields (field (name "MANUFACTURER") "Everlight") (field (name "DESIGNEDBY") "Aslı Kurt"))
      (libsource (lib "MyLibrary") (part "LED COOL WHITE 6500K 2PLCC 1411"))
    )
    (comp (ref "D122")
      (value "EAHE2835WD63")
      (footprint "LED_WHITE_1411_PLCC2")
      (description "LED Uni-Color White 39lm 6500K Chip LED 2-Pin PLCC T/R")
      (fields (field (name "MANUFACTURER") "Everlight") (field (name "DESIGNEDBY") "Aslı Kurt"))
      (libsource (lib "MyLibrary") (part "LED COOL WHITE 6500K 2PLCC 1411"))
    )
    (comp (ref "D123")
      (value "EAHE2835WD63")
      (footprint "LED_WHITE_1411_PLCC2")
      (description "LED Uni-Color White 39lm 6500K Chip LED 2-Pin PLCC T/R")
      (fields (field (name "MANUFACTURER") "Everlight") (field (name "DESIGNEDBY") "Aslı Kurt"))
      (libsource (lib "MyLibrary") (part "LED COOL WHITE 6500K 2PLCC 1411"))
    )
    (comp (ref "D124")
      (value "EAHE2835WD63")
      (footprint "LED_WHITE_1411_PLCC2")
      (description "LED Uni-Color White 39lm 6500K Chip LED 2-Pin PLCC T/R")
      (fields (field (name "MANUFACTURER") "Everlight") (field (name "DESIGNEDBY") "Aslı Kurt"))
      (libsource (lib "MyLibrary") (part "LED COOL WHITE 6500K 2PLCC 1411"))
    )
    (comp (ref "D125")
      (value "EAHE2835WD63")
      (footprint "LED_WHITE_1411_PLCC2")
      (description "LED Uni-Color White 39lm 6500K Chip LED 2-Pin PLCC T/R")
      (fields (field (name "MANUFACTURER") "Everlight") (field (name "DESIGNEDBY") "Aslı Kurt"))
      (libsource (lib "MyLibrary") (part "LED COOL WHITE 6500K 2PLCC 1411"))
    )
    (comp (ref "D126")
      (value "EAHE2835WD63")
      (footprint "LED_WHITE_1411_PLCC2")
      (description "LED Uni-Color White 39lm 6500K Chip LED 2-Pin PLCC T/R")
      (fields (field (name "MANUFACTURER") "Everlight") (field (name "DESIGNEDBY") "Aslı Kurt"))
      (libsource (lib "MyLibrary") (part "LED COOL WHITE 6500K 2PLCC 1411"))
    )
    (comp (ref "D127")
      (value "EAHE2835WD63")
      (footprint "LED_WHITE_1411_PLCC2")
      (description "LED Uni-Color White 39lm 6500K Chip LED 2-Pin PLCC T/R")
      (fields (field (name "MANUFACTURER") "Everlight") (field (name "DESIGNEDBY") "Aslı Kurt"))
      (libsource (lib "MyLibrary") (part "LED COOL WHITE 6500K 2PLCC 1411"))
    )
    (comp (ref "D128")
      (value "EAHE2835WD63")
      (footprint "LED_WHITE_1411_PLCC2")
      (description "LED Uni-Color White 39lm 6500K Chip LED 2-Pin PLCC T/R")
      (fields (field (name "MANUFACTURER") "Everlight") (field (name "DESIGNEDBY") "Aslı Kurt"))
      (libsource (lib "MyLibrary") (part "LED COOL WHITE 6500K 2PLCC 1411"))
    )
    (comp (ref "D129")
      (value "EAHE2835WD63")
      (footprint "LED_WHITE_1411_PLCC2")
      (description "LED Uni-Color White 39lm 6500K Chip LED 2-Pin PLCC T/R")
      (fields (field (name "MANUFACTURER") "Everlight") (field (name "DESIGNEDBY") "Aslı Kurt"))
      (libsource (lib "MyLibrary") (part "LED COOL WHITE 6500K 2PLCC 1411"))
    )
    (comp (ref "D130")
      (value "EAHE2835WD63")
      (footprint "LED_WHITE_1411_PLCC2")
      (description "LED Uni-Color White 39lm 6500K Chip LED 2-Pin PLCC T/R")
      (fields (field (name "MANUFACTURER") "Everlight") (field (name "DESIGNEDBY") "Aslı Kurt"))
      (libsource (lib "MyLibrary") (part "LED COOL WHITE 6500K 2PLCC 1411"))
    )
    (comp (ref "D131")
      (value "EAHE2835WD63")
      (footprint "LED_WHITE_1411_PLCC2")
      (description "LED Uni-Color White 39lm 6500K Chip LED 2-Pin PLCC T/R")
      (fields (field (name "MANUFACTURER") "Everlight") (field (name "DESIGNEDBY") "Aslı Kurt"))
      (libsource (lib "MyLibrary") (part "LED COOL WHITE 6500K 2PLCC 1411"))
    )
    (comp (ref "D132")
      (value "EAHE2835WD63")
      (footprint "LED_WHITE_1411_PLCC2")
      (description "LED Uni-Color White 39lm 6500K Chip LED 2-Pin PLCC T/R")
      (fields (field (name "MANUFACTURER") "Everlight") (field (name "DESIGNEDBY") "Aslı Kurt"))
      (libsource (lib "MyLibrary") (part "LED COOL WHITE 6500K 2PLCC 1411"))
    )
    (comp (ref "D133")
      (value "EAHE2835WD63")
      (footprint "LED_WHITE_1411_PLCC2")
      (description "LED Uni-Color White 39lm 6500K Chip LED 2-Pin PLCC T/R")
      (fields (field (name "MANUFACTURER") "Everlight") (field (name "DESIGNEDBY") "Aslı Kurt"))
      (libsource (lib "MyLibrary") (part "LED COOL WHITE 6500K 2PLCC 1411"))
    )
    (comp (ref "D134")
      (value "EAHE2835WD63")
      (footprint "LED_WHITE_1411_PLCC2")
      (description "LED Uni-Color White 39lm 6500K Chip LED 2-Pin PLCC T/R")
      (fields (field (name "MANUFACTURER") "Everlight") (field (name "DESIGNEDBY") "Aslı Kurt"))
      (libsource (lib "MyLibrary") (part "LED COOL WHITE 6500K 2PLCC 1411"))
    )
    (comp (ref "D135")
      (value "EAHE2835WD63")
      (footprint "LED_WHITE_1411_PLCC2")
      (description "LED Uni-Color White 39lm 6500K Chip LED 2-Pin PLCC T/R")
      (fields (field (name "MANUFACTURER") "Everlight") (field (name "DESIGNEDBY") "Aslı Kurt"))
      (libsource (lib "MyLibrary") (part "LED COOL WHITE 6500K 2PLCC 1411"))
    )
    (comp (ref "D136")
      (value "EAHE2835WD63")
      (footprint "LED_WHITE_1411_PLCC2")
      (description "LED Uni-Color White 39lm 6500K Chip LED 2-Pin PLCC T/R")
      (fields (field (name "MANUFACTURER") "Everlight") (field (name "DESIGNEDBY") "Aslı Kurt"))
      (libsource (lib "MyLibrary") (part "LED COOL WHITE 6500K 2PLCC 1411"))
    )
    (comp (ref "D137")
      (value "EAHE2835WD63")
      (footprint "LED_WHITE_1411_PLCC2")
      (description "LED Uni-Color White 39lm 6500K Chip LED 2-Pin PLCC T/R")
      (fields (field (name "MANUFACTURER") "Everlight") (field (name "DESIGNEDBY") "Aslı Kurt"))
      (libsource (lib "MyLibrary") (part "LED COOL WHITE 6500K 2PLCC 1411"))
    )
    (comp (ref "D138")
      (value "EAHE2835WD63")
      (footprint "LED_WHITE_1411_PLCC2")
      (description "LED Uni-Color White 39lm 6500K Chip LED 2-Pin PLCC T/R")
      (fields (field (name "MANUFACTURER") "Everlight") (field (name "DESIGNEDBY") "Aslı Kurt"))
      (libsource (lib "MyLibrary") (part "LED COOL WHITE 6500K 2PLCC 1411"))
    )
    (comp (ref "D139")
      (value "EAHE2835WD63")
      (footprint "LED_WHITE_1411_PLCC2")
      (description "LED Uni-Color White 39lm 6500K Chip LED 2-Pin PLCC T/R")
      (fields (field (name "MANUFACTURER") "Everlight") (field (name "DESIGNEDBY") "Aslı Kurt"))
      (libsource (lib "MyLibrary") (part "LED COOL WHITE 6500K 2PLCC 1411"))
    )
    (comp (ref "D140")
      (value "EAHE2835WD63")
      (footprint "LED_WHITE_1411_PLCC2")
      (description "LED Uni-Color White 39lm 6500K Chip LED 2-Pin PLCC T/R")
      (fields (field (name "MANUFACTURER") "Everlight") (field (name "DESIGNEDBY") "Aslı Kurt"))
      (libsource (lib "MyLibrary") (part "LED COOL WHITE 6500K 2PLCC 1411"))
    )
    (comp (ref "D141")
      (value "EAHE2835WD63")
      (footprint "LED_WHITE_1411_PLCC2")
      (description "LED Uni-Color White 39lm 6500K Chip LED 2-Pin PLCC T/R")
      (fields (field (name "MANUFACTURER") "Everlight") (field (name "DESIGNEDBY") "Aslı Kurt"))
      (libsource (lib "MyLibrary") (part "LED COOL WHITE 6500K 2PLCC 1411"))
    )
    (comp (ref "D142")
      (value "EAHE2835WD63")
      (footprint "LED_WHITE_1411_PLCC2")
      (description "LED Uni-Color White 39lm 6500K Chip LED 2-Pin PLCC T/R")
      (fields (field (name "MANUFACTURER") "Everlight") (field (name "DESIGNEDBY") "Aslı Kurt"))
      (libsource (lib "MyLibrary") (part "LED COOL WHITE 6500K 2PLCC 1411"))
    )
    (comp (ref "D143")
      (value "EAHE2835WD63")
      (footprint "LED_WHITE_1411_PLCC2")
      (description "LED Uni-Color White 39lm 6500K Chip LED 2-Pin PLCC T/R")
      (fields (field (name "MANUFACTURER") "Everlight") (field (name "DESIGNEDBY") "Aslı Kurt"))
      (libsource (lib "MyLibrary") (part "LED COOL WHITE 6500K 2PLCC 1411"))
    )
    (comp (ref "D144")
      (value "EAHE2835WD63")
      (footprint "LED_WHITE_1411_PLCC2")
      (description "LED Uni-Color White 39lm 6500K Chip LED 2-Pin PLCC T/R")
      (fields (field (name "MANUFACTURER") "Everlight") (field (name "DESIGNEDBY") "Aslı Kurt"))
      (libsource (lib "MyLibrary") (part "LED COOL WHITE 6500K 2PLCC 1411"))
    )
    (comp (ref "D145")
      (value "EAHE2835WD63")
      (footprint "LED_WHITE_1411_PLCC2")
      (description "LED Uni-Color White 39lm 6500K Chip LED 2-Pin PLCC T/R")
      (fields (field (name "MANUFACTURER") "Everlight") (field (name "DESIGNEDBY") "Aslı Kurt"))
      (libsource (lib "MyLibrary") (part "LED COOL WHITE 6500K 2PLCC 1411"))
    )
    (comp (ref "D146")
      (value "EAHE2835WD63")
      (footprint "LED_WHITE_1411_PLCC2")
      (description "LED Uni-Color White 39lm 6500K Chip LED 2-Pin PLCC T/R")
      (fields (field (name "MANUFACTURER") "Everlight") (field (name "DESIGNEDBY") "Aslı Kurt"))
      (libsource (lib "MyLibrary") (part "LED COOL WHITE 6500K 2PLCC 1411"))
    )
    (comp (ref "D147")
      (value "EAHE2835WD63")
      (footprint "LED_WHITE_1411_PLCC2")
      (description "LED Uni-Color White 39lm 6500K Chip LED 2-Pin PLCC T/R")
      (fields (field (name "MANUFACTURER") "Everlight") (field (name "DESIGNEDBY") "Aslı Kurt"))
      (libsource (lib "MyLibrary") (part "LED COOL WHITE 6500K 2PLCC 1411"))
    )
    (comp (ref "D148")
      (value "EAHE2835WD63")
      (footprint "LED_WHITE_1411_PLCC2")
      (description "LED Uni-Color White 39lm 6500K Chip LED 2-Pin PLCC T/R")
      (fields (field (name "MANUFACTURER") "Everlight") (field (name "DESIGNEDBY") "Aslı Kurt"))
      (libsource (lib "MyLibrary") (part "LED COOL WHITE 6500K 2PLCC 1411"))
    )
    (comp (ref "D149")
      (value "EAHE2835WD63")
      (footprint "LED_WHITE_1411_PLCC2")
      (description "LED Uni-Color White 39lm 6500K Chip LED 2-Pin PLCC T/R")
      (fields (field (name "MANUFACTURER") "Everlight") (field (name "DESIGNEDBY") "Aslı Kurt"))
      (libsource (lib "MyLibrary") (part "LED COOL WHITE 6500K 2PLCC 1411"))
    )
    (comp (ref "D150")
      (value "EAHE2835WD63")
      (footprint "LED_WHITE_1411_PLCC2")
      (description "LED Uni-Color White 39lm 6500K Chip LED 2-Pin PLCC T/R")
      (fields (field (name "MANUFACTURER") "Everlight") (field (name "DESIGNEDBY") "Aslı Kurt"))
      (libsource (lib "MyLibrary") (part "LED COOL WHITE 6500K 2PLCC 1411"))
    )
    (comp (ref "D151")
      (value "EAHE2835WD63")
      (footprint "LED_WHITE_1411_PLCC2")
      (description "LED Uni-Color White 39lm 6500K Chip LED 2-Pin PLCC T/R")
      (fields (field (name "MANUFACTURER") "Everlight") (field (name "DESIGNEDBY") "Aslı Kurt"))
      (libsource (lib "MyLibrary") (part "LED COOL WHITE 6500K 2PLCC 1411"))
    )
    (comp (ref "D152")
      (value "EAHE2835WD63")
      (footprint "LED_WHITE_1411_PLCC2")
      (description "LED Uni-Color White 39lm 6500K Chip LED 2-Pin PLCC T/R")
      (fields (field (name "MANUFACTURER") "Everlight") (field (name "DESIGNEDBY") "Aslı Kurt"))
      (libsource (lib "MyLibrary") (part "LED COOL WHITE 6500K 2PLCC 1411"))
    )
    (comp (ref "D153")
      (value "EAHE2835WD63")
      (footprint "LED_WHITE_1411_PLCC2")
      (description "LED Uni-Color White 39lm 6500K Chip LED 2-Pin PLCC T/R")
      (fields (field (name "MANUFACTURER") "Everlight") (field (name "DESIGNEDBY") "Aslı Kurt"))
      (libsource (lib "MyLibrary") (part "LED COOL WHITE 6500K 2PLCC 1411"))
    )
    (comp (ref "D154")
      (value "EAHE2835WD63")
      (footprint "LED_WHITE_1411_PLCC2")
      (description "LED Uni-Color White 39lm 6500K Chip LED 2-Pin PLCC T/R")
      (fields (field (name "MANUFACTURER") "Everlight") (field (name "DESIGNEDBY") "Aslı Kurt"))
      (libsource (lib "MyLibrary") (part "LED COOL WHITE 6500K 2PLCC 1411"))
    )
    (comp (ref "D155")
      (value "EAHE2835WD63")
      (footprint "LED_WHITE_1411_PLCC2")
      (description "LED Uni-Color White 39lm 6500K Chip LED 2-Pin PLCC T/R")
      (fields (field (name "MANUFACTURER") "Everlight") (field (name "DESIGNEDBY") "Aslı Kurt"))
      (libsource (lib "MyLibrary") (part "LED COOL WHITE 6500K 2PLCC 1411"))
    )
    (comp (ref "D156")
      (value "EAHE2835WD63")
      (footprint "LED_WHITE_1411_PLCC2")
      (description "LED Uni-Color White 39lm 6500K Chip LED 2-Pin PLCC T/R")
      (fields (field (name "MANUFACTURER") "Everlight") (field (name "DESIGNEDBY") "Aslı Kurt"))
      (libsource (lib "MyLibrary") (part "LED COOL WHITE 6500K 2PLCC 1411"))
    )
    (comp (ref "D157")
      (value "EAHE2835WD63")
      (footprint "LED_WHITE_1411_PLCC2")
      (description "LED Uni-Color White 39lm 6500K Chip LED 2-Pin PLCC T/R")
      (fields (field (name "MANUFACTURER") "Everlight") (field (name "DESIGNEDBY") "Aslı Kurt"))
      (libsource (lib "MyLibrary") (part "LED COOL WHITE 6500K 2PLCC 1411"))
    )
    (comp (ref "D158")
      (value "EAHE2835WD63")
      (footprint "LED_WHITE_1411_PLCC2")
      (description "LED Uni-Color White 39lm 6500K Chip LED 2-Pin PLCC T/R")
      (fields (field (name "MANUFACTURER") "Everlight") (field (name "DESIGNEDBY") "Aslı Kurt"))
      (libsource (lib "MyLibrary") (part "LED COOL WHITE 6500K 2PLCC 1411"))
    )
    (comp (ref "D159")
      (value "EAHE2835WD63")
      (footprint "LED_WHITE_1411_PLCC2")
      (description "LED Uni-Color White 39lm 6500K Chip LED 2-Pin PLCC T/R")
      (fields (field (name "MANUFACTURER") "Everlight") (field (name "DESIGNEDBY") "Aslı Kurt"))
      (libsource (lib "MyLibrary") (part "LED COOL WHITE 6500K 2PLCC 1411"))
    )
    (comp (ref "D160")
      (value "EAHE2835WD63")
      (footprint "LED_WHITE_1411_PLCC2")
      (description "LED Uni-Color White 39lm 6500K Chip LED 2-Pin PLCC T/R")
      (fields (field (name "MANUFACTURER") "Everlight") (field (name "DESIGNEDBY") "Aslı Kurt"))
      (libsource (lib "MyLibrary") (part "LED COOL WHITE 6500K 2PLCC 1411"))
    )
    (comp (ref "D161")
      (value "EAHE2835WD63")
      (footprint "LED_WHITE_1411_PLCC2")
      (description "LED Uni-Color White 39lm 6500K Chip LED 2-Pin PLCC T/R")
      (fields (field (name "MANUFACTURER") "Everlight") (field (name "DESIGNEDBY") "Aslı Kurt"))
      (libsource (lib "MyLibrary") (part "LED COOL WHITE 6500K 2PLCC 1411"))
    )
    (comp (ref "D162")
      (value "EAHE2835WD63")
      (footprint "LED_WHITE_1411_PLCC2")
      (description "LED Uni-Color White 39lm 6500K Chip LED 2-Pin PLCC T/R")
      (fields (field (name "MANUFACTURER") "Everlight") (field (name "DESIGNEDBY") "Aslı Kurt"))
      (libsource (lib "MyLibrary") (part "LED COOL WHITE 6500K 2PLCC 1411"))
    )
    (comp (ref "D163")
      (value "EAHE2835WD63")
      (footprint "LED_WHITE_1411_PLCC2")
      (description "LED Uni-Color White 39lm 6500K Chip LED 2-Pin PLCC T/R")
      (fields (field (name "MANUFACTURER") "Everlight") (field (name "DESIGNEDBY") "Aslı Kurt"))
      (libsource (lib "MyLibrary") (part "LED COOL WHITE 6500K 2PLCC 1411"))
    )
    (comp (ref "D164")
      (value "EAHE2835WD63")
      (footprint "LED_WHITE_1411_PLCC2")
      (description "LED Uni-Color White 39lm 6500K Chip LED 2-Pin PLCC T/R")
      (fields (field (name "MANUFACTURER") "Everlight") (field (name "DESIGNEDBY") "Aslı Kurt"))
      (libsource (lib "MyLibrary") (part "LED COOL WHITE 6500K 2PLCC 1411"))
    )
    (comp (ref "D165")
      (value "EAHE2835WD63")
      (footprint "LED_WHITE_1411_PLCC2")
      (description "LED Uni-Color White 39lm 6500K Chip LED 2-Pin PLCC T/R")
      (fields (field (name "MANUFACTURER") "Everlight") (field (name "DESIGNEDBY") "Aslı Kurt"))
      (libsource (lib "MyLibrary") (part "LED COOL WHITE 6500K 2PLCC 1411"))
    )
    (comp (ref "D166")
      (value "EAHE2835WD63")
      (footprint "LED_WHITE_1411_PLCC2")
      (description "LED Uni-Color White 39lm 6500K Chip LED 2-Pin PLCC T/R")
      (fields (field (name "MANUFACTURER") "Everlight") (field (name "DESIGNEDBY") "Aslı Kurt"))
      (libsource (lib "MyLibrary") (part "LED COOL WHITE 6500K 2PLCC 1411"))
    )
    (comp (ref "D167")
      (value "EAHE2835WD63")
      (footprint "LED_WHITE_1411_PLCC2")
      (description "LED Uni-Color White 39lm 6500K Chip LED 2-Pin PLCC T/R")
      (fields (field (name "MANUFACTURER") "Everlight") (field (name "DESIGNEDBY") "Aslı Kurt"))
      (libsource (lib "MyLibrary") (part "LED COOL WHITE 6500K 2PLCC 1411"))
    )
    (comp (ref "D168")
      (value "EAHE2835WD63")
      (footprint "LED_WHITE_1411_PLCC2")
      (description "LED Uni-Color White 39lm 6500K Chip LED 2-Pin PLCC T/R")
      (fields (field (name "MANUFACTURER") "Everlight") (field (name "DESIGNEDBY") "Aslı Kurt"))
      (libsource (lib "MyLibrary") (part "LED COOL WHITE 6500K 2PLCC 1411"))
    )
    (comp (ref "D169")
      (value "EAHE2835WD63")
      (footprint "LED_WHITE_1411_PLCC2")
      (description "LED Uni-Color White 39lm 6500K Chip LED 2-Pin PLCC T/R")
      (fields (field (name "MANUFACTURER") "Everlight") (field (name "DESIGNEDBY") "Aslı Kurt"))
      (libsource (lib "MyLibrary") (part "LED COOL WHITE 6500K 2PLCC 1411"))
    )
    (comp (ref "D170")
      (value "EAHE2835WD63")
      (footprint "LED_WHITE_1411_PLCC2")
      (description "LED Uni-Color White 39lm 6500K Chip LED 2-Pin PLCC T/R")
      (fields (field (name "MANUFACTURER") "Everlight") (field (name "DESIGNEDBY") "Aslı Kurt"))
      (libsource (lib "MyLibrary") (part "LED COOL WHITE 6500K 2PLCC 1411"))
    )
    (comp (ref "D171")
      (value "EAHE2835WD63")
      (footprint "LED_WHITE_1411_PLCC2")
      (description "LED Uni-Color White 39lm 6500K Chip LED 2-Pin PLCC T/R")
      (fields (field (name "MANUFACTURER") "Everlight") (field (name "DESIGNEDBY") "Aslı Kurt"))
      (libsource (lib "MyLibrary") (part "LED COOL WHITE 6500K 2PLCC 1411"))
    )
    (comp (ref "R9")
      (value "HRG3216Q-20R0-D-T1")
      (footprint "RES_1206")
      (description "Fixed Resistor, Thin Film, 1W, 20ohm, 200V, 0.5% +/-Tol, 50ppm/Cel, Surface Mount, 1206")
      (fields
        (field (name "MANUFACTURER") "Susumu")
        (field (name "RESISTANCE") "20R")
        (field (name "DESIGNEDBY") "Aslı Kurt")
      )
      (libsource (lib "MyLibrary") (part "RES 20 OHM 1206 1W"))
    )
    (comp (ref "R10")
      (value "HRG3216Q-20R0-D-T1")
      (footprint "RES_1206")
      (description "Fixed Resistor, Thin Film, 1W, 20ohm, 200V, 0.5% +/-Tol, 50ppm/Cel, Surface Mount, 1206")
      (fields
        (field (name "MANUFACTURER") "Susumu")
        (field (name "RESISTANCE") "20R")
        (field (name "DESIGNEDBY") "Aslı Kurt")
      )
      (libsource (lib "MyLibrary") (part "RES 20 OHM 1206 1W"))
    )
    (comp (ref "R11")
      (value "HRG3216Q-20R0-D-T1")
      (footprint "RES_1206")
      (description "Fixed Resistor, Thin Film, 1W, 20ohm, 200V, 0.5% +/-Tol, 50ppm/Cel, Surface Mount, 1206")
      (fields
        (field (name "MANUFACTURER") "Susumu")
        (field (name "RESISTANCE") "20R")
        (field (name "DESIGNEDBY") "Aslı Kurt")
      )
      (libsource (lib "MyLibrary") (part "RES 20 OHM 1206 1W"))
    )
    (comp (ref "R12")
      (value "HRG3216Q-20R0-D-T1")
      (footprint "RES_1206")
      (description "Fixed Resistor, Thin Film, 1W, 20ohm, 200V, 0.5% +/-Tol, 50ppm/Cel, Surface Mount, 1206")
      (fields
        (field (name "MANUFACTURER") "Susumu")
        (field (name "RESISTANCE") "20R")
        (field (name "DESIGNEDBY") "Aslı Kurt")
      )
      (libsource (lib "MyLibrary") (part "RES 20 OHM 1206 1W"))
    )
    (comp (ref "R13")
      (value "HRG3216Q-20R0-D-T1")
      (footprint "RES_1206")
      (description "Fixed Resistor, Thin Film, 1W, 20ohm, 200V, 0.5% +/-Tol, 50ppm/Cel, Surface Mount, 1206")
      (fields
        (field (name "MANUFACTURER") "Susumu")
        (field (name "RESISTANCE") "20R")
        (field (name "DESIGNEDBY") "Aslı Kurt")
      )
      (libsource (lib "MyLibrary") (part "RES 20 OHM 1206 1W"))
    )
    (comp (ref "R14")
      (value "HRG3216Q-20R0-D-T1")
      (footprint "RES_1206")
      (description "Fixed Resistor, Thin Film, 1W, 20ohm, 200V, 0.5% +/-Tol, 50ppm/Cel, Surface Mount, 1206")
      (fields
        (field (name "MANUFACTURER") "Susumu")
        (field (name "RESISTANCE") "20R")
        (field (name "DESIGNEDBY") "Aslı Kurt")
      )
      (libsource (lib "MyLibrary") (part "RES 20 OHM 1206 1W"))
    )
    (comp (ref "R15")
      (value "HRG3216Q-20R0-D-T1")
      (footprint "RES_1206")
      (description "Fixed Resistor, Thin Film, 1W, 20ohm, 200V, 0.5% +/-Tol, 50ppm/Cel, Surface Mount, 1206")
      (fields
        (field (name "MANUFACTURER") "Susumu")
        (field (name "RESISTANCE") "20R")
        (field (name "DESIGNEDBY") "Aslı Kurt")
      )
      (libsource (lib "MyLibrary") (part "RES 20 OHM 1206 1W"))
    )
    (comp (ref "R16")
      (value "HRG3216Q-20R0-D-T1")
      (footprint "RES_1206")
      (description "Fixed Resistor, Thin Film, 1W, 20ohm, 200V, 0.5% +/-Tol, 50ppm/Cel, Surface Mount, 1206")
      (fields
        (field (name "MANUFACTURER") "Susumu")
        (field (name "RESISTANCE") "20R")
        (field (name "DESIGNEDBY") "Aslı Kurt")
      )
      (libsource (lib "MyLibrary") (part "RES 20 OHM 1206 1W"))
    )
    (comp (ref "R17")
      (value "HRG3216Q-20R0-D-T1")
      (footprint "RES_1206")
      (description "Fixed Resistor, Thin Film, 1W, 20ohm, 200V, 0.5% +/-Tol, 50ppm/Cel, Surface Mount, 1206")
      (fields
        (field (name "MANUFACTURER") "Susumu")
        (field (name "RESISTANCE") "20R")
        (field (name "DESIGNEDBY") "Aslı Kurt")
      )
      (libsource (lib "MyLibrary") (part "RES 20 OHM 1206 1W"))
    )
    (comp (ref "R18")
      (value "HRG3216Q-20R0-D-T1")
      (footprint "RES_1206")
      (description "Fixed Resistor, Thin Film, 1W, 20ohm, 200V, 0.5% +/-Tol, 50ppm/Cel, Surface Mount, 1206")
      (fields
        (field (name "MANUFACTURER") "Susumu")
        (field (name "RESISTANCE") "20R")
        (field (name "DESIGNEDBY") "Aslı Kurt")
      )
      (libsource (lib "MyLibrary") (part "RES 20 OHM 1206 1W"))
    )
    (comp (ref "R19")
      (value "HRG3216Q-20R0-D-T1")
      (footprint "RES_1206")
      (description "Fixed Resistor, Thin Film, 1W, 20ohm, 200V, 0.5% +/-Tol, 50ppm/Cel, Surface Mount, 1206")
      (fields
        (field (name "MANUFACTURER") "Susumu")
        (field (name "RESISTANCE") "20R")
        (field (name "DESIGNEDBY") "Aslı Kurt")
      )
      (libsource (lib "MyLibrary") (part "RES 20 OHM 1206 1W"))
    )
    (comp (ref "R20")
      (value "HRG3216Q-20R0-D-T1")
      (footprint "RES_1206")
      (description "Fixed Resistor, Thin Film, 1W, 20ohm, 200V, 0.5% +/-Tol, 50ppm/Cel, Surface Mount, 1206")
      (fields
        (field (name "MANUFACTURER") "Susumu")
        (field (name "RESISTANCE") "20R")
        (field (name "DESIGNEDBY") "Aslı Kurt")
      )
      (libsource (lib "MyLibrary") (part "RES 20 OHM 1206 1W"))
    )
    (comp (ref "R21")
      (value "HRG3216Q-20R0-D-T1")
      (footprint "RES_1206")
      (description "Fixed Resistor, Thin Film, 1W, 20ohm, 200V, 0.5% +/-Tol, 50ppm/Cel, Surface Mount, 1206")
      (fields
        (field (name "MANUFACTURER") "Susumu")
        (field (name "RESISTANCE") "20R")
        (field (name "DESIGNEDBY") "Aslı Kurt")
      )
      (libsource (lib "MyLibrary") (part "RES 20 OHM 1206 1W"))
    )
    (comp (ref "R22")
      (value "HRG3216Q-20R0-D-T1")
      (footprint "RES_1206")
      (description "Fixed Resistor, Thin Film, 1W, 20ohm, 200V, 0.5% +/-Tol, 50ppm/Cel, Surface Mount, 1206")
      (fields
        (field (name "MANUFACTURER") "Susumu")
        (field (name "RESISTANCE") "20R")
        (field (name "DESIGNEDBY") "Aslı Kurt")
      )
      (libsource (lib "MyLibrary") (part "RES 20 OHM 1206 1W"))
    )
    (comp (ref "R23")
      (value "HRG3216Q-20R0-D-T1")
      (footprint "RES_1206")
      (description "Fixed Resistor, Thin Film, 1W, 20ohm, 200V, 0.5% +/-Tol, 50ppm/Cel, Surface Mount, 1206")
      (fields
        (field (name "MANUFACTURER") "Susumu")
        (field (name "RESISTANCE") "20R")
        (field (name "DESIGNEDBY") "Aslı Kurt")
      )
      (libsource (lib "MyLibrary") (part "RES 20 OHM 1206 1W"))
    )
    (comp (ref "R24")
      (value "HRG3216Q-20R0-D-T1")
      (footprint "RES_1206")
      (description "Fixed Resistor, Thin Film, 1W, 20ohm, 200V, 0.5% +/-Tol, 50ppm/Cel, Surface Mount, 1206")
      (fields
        (field (name "MANUFACTURER") "Susumu")
        (field (name "RESISTANCE") "20R")
        (field (name "DESIGNEDBY") "Aslı Kurt")
      )
      (libsource (lib "MyLibrary") (part "RES 20 OHM 1206 1W"))
    )
    (comp (ref "R25")
      (value "HRG3216Q-20R0-D-T1")
      (footprint "RES_1206")
      (description "Fixed Resistor, Thin Film, 1W, 20ohm, 200V, 0.5% +/-Tol, 50ppm/Cel, Surface Mount, 1206")
      (fields
        (field (name "MANUFACTURER") "Susumu")
        (field (name "RESISTANCE") "20R")
        (field (name "DESIGNEDBY") "Aslı Kurt")
      )
      (libsource (lib "MyLibrary") (part "RES 20 OHM 1206 1W"))
    )
    (comp (ref "R26")
      (value "HRG3216Q-20R0-D-T1")
      (footprint "RES_1206")
      (description "Fixed Resistor, Thin Film, 1W, 20ohm, 200V, 0.5% +/-Tol, 50ppm/Cel, Surface Mount, 1206")
      (fields
        (field (name "MANUFACTURER") "Susumu")
        (field (name "RESISTANCE") "20R")
        (field (name "DESIGNEDBY") "Aslı Kurt")
      )
      (libsource (lib "MyLibrary") (part "RES 20 OHM 1206 1W"))
    )
    (comp (ref "R27")
      (value "HRG3216Q-20R0-D-T1")
      (footprint "RES_1206")
      (description "Fixed Resistor, Thin Film, 1W, 20ohm, 200V, 0.5% +/-Tol, 50ppm/Cel, Surface Mount, 1206")
      (fields
        (field (name "MANUFACTURER") "Susumu")
        (field (name "RESISTANCE") "20R")
        (field (name "DESIGNEDBY") "Aslı Kurt")
      )
      (libsource (lib "MyLibrary") (part "RES 20 OHM 1206 1W"))
    )
    (comp (ref "R28")
      (value "HRG3216Q-20R0-D-T1")
      (footprint "RES_1206")
      (description "Fixed Resistor, Thin Film, 1W, 20ohm, 200V, 0.5% +/-Tol, 50ppm/Cel, Surface Mount, 1206")
      (fields
        (field (name "MANUFACTURER") "Susumu")
        (field (name "RESISTANCE") "20R")
        (field (name "DESIGNEDBY") "Aslı Kurt")
      )
      (libsource (lib "MyLibrary") (part "RES 20 OHM 1206 1W"))
    )
    (comp (ref "R29")
      (value "HRG3216Q-20R0-D-T1")
      (footprint "RES_1206")
      (description "Fixed Resistor, Thin Film, 1W, 20ohm, 200V, 0.5% +/-Tol, 50ppm/Cel, Surface Mount, 1206")
      (fields
        (field (name "MANUFACTURER") "Susumu")
        (field (name "RESISTANCE") "20R")
        (field (name "DESIGNEDBY") "Aslı Kurt")
      )
      (libsource (lib "MyLibrary") (part "RES 20 OHM 1206 1W"))
    )
    (comp (ref "R30")
      (value "HRG3216Q-20R0-D-T1")
      (footprint "RES_1206")
      (description "Fixed Resistor, Thin Film, 1W, 20ohm, 200V, 0.5% +/-Tol, 50ppm/Cel, Surface Mount, 1206")
      (fields
        (field (name "MANUFACTURER") "Susumu")
        (field (name "RESISTANCE") "20R")
        (field (name "DESIGNEDBY") "Aslı Kurt")
      )
      (libsource (lib "MyLibrary") (part "RES 20 OHM 1206 1W"))
    )
    (comp (ref "R31")
      (value "HRG3216Q-20R0-D-T1")
      (footprint "RES_1206")
      (description "Fixed Resistor, Thin Film, 1W, 20ohm, 200V, 0.5% +/-Tol, 50ppm/Cel, Surface Mount, 1206")
      (fields
        (field (name "MANUFACTURER") "Susumu")
        (field (name "RESISTANCE") "20R")
        (field (name "DESIGNEDBY") "Aslı Kurt")
      )
      (libsource (lib "MyLibrary") (part "RES 20 OHM 1206 1W"))
    )
    (comp (ref "R32")
      (value "HRG3216Q-20R0-D-T1")
      (footprint "RES_1206")
      (description "Fixed Resistor, Thin Film, 1W, 20ohm, 200V, 0.5% +/-Tol, 50ppm/Cel, Surface Mount, 1206")
      (fields
        (field (name "MANUFACTURER") "Susumu")
        (field (name "RESISTANCE") "20R")
        (field (name "DESIGNEDBY") "Aslı Kurt")
      )
      (libsource (lib "MyLibrary") (part "RES 20 OHM 1206 1W"))
    )
  )
  (nets
    (net (code "1") (name "/COL1") (class "Default")
      (node (ref "R9") (pin "2") (pinfunction "2_2") (pintype "passive"))
    )
    (net (code "2") (name "/COL2") (class "Default")
      (node (ref "R10") (pin "2") (pinfunction "2_2") (pintype "passive"))
    )
    (net (code "3") (name "/COL3") (class "Default")
      (node (ref "R11") (pin "2") (pinfunction "2_2") (pintype "passive"))
    )
    (net (code "4") (name "/COL4") (class "Default")
      (node (ref "R12") (pin "2") (pinfunction "2_2") (pintype "passive"))
    )
    (net (code "5") (name "/COL5") (class "Default")
      (node (ref "R13") (pin "2") (pinfunction "2_2") (pintype "passive"))
    )
    (net (code "6") (name "/COL6") (class "Default")
      (node (ref "R14") (pin "2") (pinfunction "2_2") (pintype "passive"))
    )
    (net (code "7") (name "/COL7") (class "Default")
      (node (ref "R15") (pin "2") (pinfunction "2_2") (pintype "passive"))
    )
    (net (code "8") (name "/COL8") (class "Default")
      (node (ref "R16") (pin "2") (pinfunction "2_2") (pintype "passive"))
    )
    (net (code "9") (name "/COL9") (class "Default")
      (node (ref "R17") (pin "2") (pinfunction "2_2") (pintype "passive"))
    )
    (net (code "10") (name "/COL10") (class "Default")
      (node (ref "R18") (pin "2") (pinfunction "2_2") (pintype "passive"))
    )
    (net (code "11") (name "/COL11") (class "Default")
      (node (ref "R19") (pin "2") (pinfunction "2_2") (pintype "passive"))
    )
    (net (code "12") (name "/COL12") (class "Default")
      (node (ref "R20") (pin "2") (pinfunction "2_2") (pintype "passive"))
    )
    (net (code "13") (name "/COL13") (class "Default")
      (node (ref "R21") (pin "2") (pinfunction "2_2") (pintype "passive"))
    )
    (net (code "14") (name "/COL14") (class "Default")
      (node (ref "R22") (pin "2") (pinfunction "2_2") (pintype "passive"))
    )
    (net (code "15") (name "/COL15") (class "Default")
      (node (ref "R23") (pin "2") (pinfunction "2_2") (pintype "passive"))
    )
    (net (code "16") (name "/COL16") (class "Default")
      (node (ref "R24") (pin "2") (pinfunction "2_2") (pintype "passive"))
    )
    (net (code "17") (name "/COL17") (class "Default")
      (node (ref "R25") (pin "2") (pinfunction "2_2") (pintype "passive"))
    )
    (net (code "18") (name "/COL18") (class "Default")
      (node (ref "R26") (pin "2") (pinfunction "2_2") (pintype "passive"))
    )
    (net (code "19") (name "/COL19") (class "Default")
      (node (ref "R27") (pin "2") (pinfunction "2_2") (pintype "passive"))
    )
    (net (code "20") (name "/COL20") (class "Default")
      (node (ref "R28") (pin "2") (pinfunction "2_2") (pintype "passive"))
    )
    (net (code "21") (name "/COL21") (class "Default")
      (node (ref "R29") (pin "2") (pinfunction "2_2") (pintype "passive"))
    )
    (net (code "22") (name "/COL22") (class "Default")
      (node (ref "R30") (pin "2") (pinfunction "2_2") (pintype "passive"))
    )
    (net (code "23") (name "/COL23") (class "Default")
      (node (ref "R31") (pin "2") (pinfunction "2_2") (pintype "passive"))
    )
    (net (code "24") (name "/COL24") (class "Default")
      (node (ref "R32") (pin "2") (pinfunction "2_2") (pintype "passive"))
    )
    (net (code "25") (name "/ROW1") (class "Default")
      (node (ref "D10") (pin "2") (pinfunction "2_2") (pintype "power_in"))
      (node (ref "D11") (pin "2") (pinfunction "2_2") (pintype "power_in"))
      (node (ref "D12") (pin "2") (pinfunction "2_2") (pintype "power_in"))
      (node (ref "D13") (pin "2") (pinfunction "2_2") (pintype "power_in"))
      (node (ref "D14") (pin "2") (pinfunction "2_2") (pintype "power_in"))
      (node (ref "D15") (pin "2") (pinfunction "2_2") (pintype "power_in"))
      (node (ref "D16") (pin "2") (pinfunction "2_2") (pintype "power_in"))
      (node (ref "D17") (pin "2") (pinfunction "2_2") (pintype "power_in"))
      (node (ref "D18") (pin "2") (pinfunction "2_2") (pintype "power_in"))
      (node (ref "D19") (pin "2") (pinfunction "2_2") (pintype "power_in"))
      (node (ref "D20") (pin "2") (pinfunction "2_2") (pintype "power_in"))
      (node (ref "D21") (pin "2") (pinfunction "2_2") (pintype "power_in"))
      (node (ref "D22") (pin "2") (pinfunction "2_2") (pintype "power_in"))
      (node (ref "D23") (pin "2") (pinfunction "2_2") (pintype "power_in"))
      (node (ref "D24") (pin "2") (pinfunction "2_2") (pintype "power_in"))
      (node (ref "D25") (pin "2") (pinfunction "2_2") (pintype "power_in"))
      (node (ref "D26") (pin "2") (pinfunction "2_2") (pintype "power_in"))
      (node (ref "D27") (pin "2") (pinfunction "2_2") (pintype "power_in"))
      (node (ref "D4") (pin "2") (pinfunction "2_2") (pintype "power_in"))
      (node (ref "D5") (pin "2") (pinfunction "2_2") (pintype "power_in"))
      (node (ref "D6") (pin "2") (pinfunction "2_2") (pintype "power_in"))
      (node (ref "D7") (pin "2") (pinfunction "2_2") (pintype "power_in"))
      (node (ref "D8") (pin "2") (pinfunction "2_2") (pintype "power_in"))
      (node (ref "D9") (pin "2") (pinfunction "2_2") (pintype "power_in"))
    )
    (net (code "26") (name "/ROW2") (class "Default")
      (node (ref "D28") (pin "2") (pinfunction "2_2") (pintype "power_in"))
      (node (ref "D29") (pin "2") (pinfunction "2_2") (pintype "power_in"))
      (node (ref "D30") (pin "2") (pinfunction "2_2") (pintype "power_in"))
      (node (ref "D31") (pin "2") (pinfunction "2_2") (pintype "power_in"))
      (node (ref "D32") (pin "2") (pinfunction "2_2") (pintype "power_in"))
      (node (ref "D33") (pin "2") (pinfunction "2_2") (pintype "power_in"))
      (node (ref "D34") (pin "2") (pinfunction "2_2") (pintype "power_in"))
      (node (ref "D35") (pin "2") (pinfunction "2_2") (pintype "power_in"))
      (node (ref "D36") (pin "2") (pinfunction "2_2") (pintype "power_in"))
      (node (ref "D37") (pin "2") (pinfunction "2_2") (pintype "power_in"))
      (node (ref "D38") (pin "2") (pinfunction "2_2") (pintype "power_in"))
      (node (ref "D39") (pin "2") (pinfunction "2_2") (pintype "power_in"))
      (node (ref "D40") (pin "2") (pinfunction "2_2") (pintype "power_in"))
      (node (ref "D41") (pin "2") (pinfunction "2_2") (pintype "power_in"))
      (node (ref "D42") (pin "2") (pinfunction "2_2") (pintype "power_in"))
      (node (ref "D43") (pin "2") (pinfunction "2_2") (pintype "power_in"))
      (node (ref "D44") (pin "2") (pinfunction "2_2") (pintype "power_in"))
      (node (ref "D45") (pin "2") (pinfunction "2_2") (pintype "power_in"))
      (node (ref "D46") (pin "2") (pinfunction "2_2") (pintype "power_in"))
      (node (ref "D47") (pin "2") (pinfunction "2_2") (pintype "power_in"))
      (node (ref "D48") (pin "2") (pinfunction "2_2") (pintype "power_in"))
      (node (ref "D49") (pin "2") (pinfunction "2_2") (pintype "power_in"))
      (node (ref "D50") (pin "2") (pinfunction "2_2") (pintype "power_in"))
      (node (ref "D51") (pin "2") (pinfunction "2_2") (pintype "power_in"))
    )
    (net (code "27") (name "/ROW3") (class "Default")
      (node (ref "D52") (pin "2") (pinfunction "2_2") (pintype "power_in"))
      (node (ref "D53") (pin "2") (pinfunction "2_2") (pintype "power_in"))
      (node (ref "D54") (pin "2") (pinfunction "2_2") (pintype "power_in"))
      (node (ref "D55") (pin "2") (pinfunction "2_2") (pintype "power_in"))
      (node (ref "D56") (pin "2") (pinfunction "2_2") (pintype "power_in"))
      (node (ref "D57") (pin "2") (pinfunction "2_2") (pintype "power_in"))
      (node (ref "D58") (pin "2") (pinfunction "2_2") (pintype "power_in"))
      (node (ref "D59") (pin "2") (pinfunction "2_2") (pintype "power_in"))
      (node (ref "D60") (pin "2") (pinfunction "2_2") (pintype "power_in"))
      (node (ref "D61") (pin "2") (pinfunction "2_2") (pintype "power_in"))
      (node (ref "D62") (pin "2") (pinfunction "2_2") (pintype "power_in"))
      (node (ref "D63") (pin "2") (pinfunction "2_2") (pintype "power_in"))
      (node (ref "D64") (pin "2") (pinfunction "2_2") (pintype "power_in"))
      (node (ref "D65") (pin "2") (pinfunction "2_2") (pintype "power_in"))
      (node (ref "D66") (pin "2") (pinfunction "2_2") (pintype "power_in"))
      (node (ref "D67") (pin "2") (pinfunction "2_2") (pintype "power_in"))
      (node (ref "D68") (pin "2") (pinfunction "2_2") (pintype "power_in"))
      (node (ref "D69") (pin "2") (pinfunction "2_2") (pintype "power_in"))
      (node (ref "D70") (pin "2") (pinfunction "2_2") (pintype "power_in"))
      (node (ref "D71") (pin "2") (pinfunction "2_2") (pintype "power_in"))
      (node (ref "D72") (pin "2") (pinfunction "2_2") (pintype "power_in"))
      (node (ref "D73") (pin "2") (pinfunction "2_2") (pintype "power_in"))
      (node (ref "D74") (pin "2") (pinfunction "2_2") (pintype "power_in"))
      (node (ref "D75") (pin "2") (pinfunction "2_2") (pintype "power_in"))
    )
    (net (code "28") (name "/ROW4") (class "Default")
      (node (ref "D76") (pin "2") (pinfunction "2_2") (pintype "power_in"))
      (node (ref "D77") (pin "2") (pinfunction "2_2") (pintype "power_in"))
      (node (ref "D78") (pin "2") (pinfunction "2_2") (pintype "power_in"))
      (node (ref "D79") (pin "2") (pinfunction "2_2") (pintype "power_in"))
      (node (ref "D80") (pin "2") (pinfunction "2_2") (pintype "power_in"))
      (node (ref "D81") (pin "2") (pinfunction "2_2") (pintype "power_in"))
      (node (ref "D82") (pin "2") (pinfunction "2_2") (pintype "power_in"))
      (node (ref "D83") (pin "2") (pinfunction "2_2") (pintype "power_in"))
      (node (ref "D84") (pin "2") (pinfunction "2_2") (pintype "power_in"))
      (node (ref "D85") (pin "2") (pinfunction "2_2") (pintype "power_in"))
      (node (ref "D86") (pin "2") (pinfunction "2_2") (pintype "power_in"))
      (node (ref "D87") (pin "2") (pinfunction "2_2") (pintype "power_in"))
      (node (ref "D88") (pin "2") (pinfunction "2_2") (pintype "power_in"))
      (node (ref "D89") (pin "2") (pinfunction "2_2") (pintype "power_in"))
      (node (ref "D90") (pin "2") (pinfunction "2_2") (pintype "power_in"))
      (node (ref "D91") (pin "2") (pinfunction "2_2") (pintype "power_in"))
      (node (ref "D92") (pin "2") (pinfunction "2_2") (pintype "power_in"))
      (node (ref "D93") (pin "2") (pinfunction "2_2") (pintype "power_in"))
      (node (ref "D94") (pin "2") (pinfunction "2_2") (pintype "power_in"))
      (node (ref "D95") (pin "2") (pinfunction "2_2") (pintype "power_in"))
      (node (ref "D96") (pin "2") (pinfunction "2_2") (pintype "power_in"))
      (node (ref "D97") (pin "2") (pinfunction "2_2") (pintype "power_in"))
      (node (ref "D98") (pin "2") (pinfunction "2_2") (pintype "power_in"))
      (node (ref "D99") (pin "2") (pinfunction "2_2") (pintype "power_in"))
    )
    (net (code "29") (name "/ROW5") (class "Default")
      (node (ref "D100") (pin "2") (pinfunction "2_2") (pintype "power_in"))
      (node (ref "D101") (pin "2") (pinfunction "2_2") (pintype "power_in"))
      (node (ref "D102") (pin "2") (pinfunction "2_2") (pintype "power_in"))
      (node (ref "D103") (pin "2") (pinfunction "2_2") (pintype "power_in"))
      (node (ref "D104") (pin "2") (pinfunction "2_2") (pintype "power_in"))
      (node (ref "D105") (pin "2") (pinfunction "2_2") (pintype "power_in"))
      (node (ref "D106") (pin "2") (pinfunction "2_2") (pintype "power_in"))
      (node (ref "D107") (pin "2") (pinfunction "2_2") (pintype "power_in"))
      (node (ref "D108") (pin "2") (pinfunction "2_2") (pintype "power_in"))
      (node (ref "D109") (pin "2") (pinfunction "2_2") (pintype "power_in"))
      (node (ref "D110") (pin "2") (pinfunction "2_2") (pintype "power_in"))
      (node (ref "D111") (pin "2") (pinfunction "2_2") (pintype "power_in"))
      (node (ref "D112") (pin "2") (pinfunction "2_2") (pintype "power_in"))
      (node (ref "D113") (pin "2") (pinfunction "2_2") (pintype "power_in"))
      (node (ref "D114") (pin "2") (pinfunction "2_2") (pintype "power_in"))
      (node (ref "D115") (pin "2") (pinfunction "2_2") (pintype "power_in"))
      (node (ref "D116") (pin "2") (pinfunction "2_2") (pintype "power_in"))
      (node (ref "D117") (pin "2") (pinfunction "2_2") (pintype "power_in"))
      (node (ref "D118") (pin "2") (pinfunction "2_2") (pintype "power_in"))
      (node (ref "D119") (pin "2") (pinfunction "2_2") (pintype "power_in"))
      (node (ref "D120") (pin "2") (pinfunction "2_2") (pintype "power_in"))
      (node (ref "D121") (pin "2") (pinfunction "2_2") (pintype "power_in"))
      (node (ref "D122") (pin "2") (pinfunction "2_2") (pintype "power_in"))
      (node (ref "D123") (pin "2") (pinfunction "2_2") (pintype "power_in"))
    )
    (net (code "30") (name "/ROW6") (class "Default")
      (node (ref "D124") (pin "2") (pinfunction "2_2") (pintype "power_in"))
      (node (ref "D125") (pin "2") (pinfunction "2_2") (pintype "power_in"))
      (node (ref "D126") (pin "2") (pinfunction "2_2") (pintype "power_in"))
      (node (ref "D127") (pin "2") (pinfunction "2_2") (pintype "power_in"))
      (node (ref "D128") (pin "2") (pinfunction "2_2") (pintype "power_in"))
      (node (ref "D129") (pin "2") (pinfunction "2_2") (pintype "power_in"))
      (node (ref "D130") (pin "2") (pinfunction "2_2") (pintype "power_in"))
      (node (ref "D131") (pin "2") (pinfunction "2_2") (pintype "power_in"))
      (node (ref "D132") (pin "2") (pinfunction "2_2") (pintype "power_in"))
      (node (ref "D133") (pin "2") (pinfunction "2_2") (pintype "power_in"))
      (node (ref "D134") (pin "2") (pinfunction "2_2") (pintype "power_in"))
      (node (ref "D135") (pin "2") (pinfunction "2_2") (pintype "power_in"))
      (node (ref "D136") (pin "2") (pinfunction "2_2") (pintype "power_in"))
      (node (ref "D137") (pin "2") (pinfunction "2_2") (pintype "power_in"))
      (node (ref "D138") (pin "2") (pinfunction "2_2") (pintype "power_in"))
      (node (ref "D139") (pin "2") (pinfunction "2_2") (pintype "power_in"))
      (node (ref "D140") (pin "2") (pinfunction "2_2") (pintype "power_in"))
      (node (ref "D141") (pin "2") (pinfunction "2_2") (pintype "power_in"))
      (node (ref "D142") (pin "2") (pinfunction "2_2") (pintype "power_in"))
      (node (ref "D143") (pin "2") (pinfunction "2_2") (pintype "power_in"))
      (node (ref "D144") (pin "2") (pinfunction "2_2") (pintype "power_in"))
      (node (ref "D145") (pin "2") (pinfunction "2_2") (pintype "power_in"))
      (node (ref "D146") (pin "2") (pinfunction "2_2") (pintype "power_in"))
      (node (ref "D147") (pin "2") (pinfunction "2_2") (pintype "power_in"))
    )
    (net (code "31") (name "/ROW7") (class "Default")
      (node (ref "D148") (pin "2") (pinfunction "2_2") (pintype "power_in"))
      (node (ref "D149") (pin "2") (pinfunction "2_2") (pintype "power_in"))
      (node (ref "D150") (pin "2") (pinfunction "2_2") (pintype "power_in"))
      (node (ref "D151") (pin "2") (pinfunction "2_2") (pintype "power_in"))
      (node (ref "D152") (pin "2") (pinfunction "2_2") (pintype "power_in"))
      (node (ref "D153") (pin "2") (pinfunction "2_2") (pintype "power_in"))
      (node (ref "D154") (pin "2") (pinfunction "2_2") (pintype "power_in"))
      (node (ref "D155") (pin "2") (pinfunction "2_2") (pintype "power_in"))
      (node (ref "D156") (pin "2") (pinfunction "2_2") (pintype "power_in"))
      (node (ref "D157") (pin "2") (pinfunction "2_2") (pintype "power_in"))
      (node (ref "D158") (pin "2") (pinfunction "2_2") (pintype "power_in"))
      (node (ref "D159") (pin "2") (pinfunction "2_2") (pintype "power_in"))
      (node (ref "D160") (pin "2") (pinfunction "2_2") (pintype "power_in"))
      (node (ref "D161") (pin "2") (pinfunction "2_2") (pintype "power_in"))
      (node (ref "D162") (pin "2") (pinfunction "2_2") (pintype "power_in"))
      (node (ref "D163") (pin "2") (pinfunction "2_2") (pintype "power_in"))
      (node (ref "D164") (pin "2") (pinfunction "2_2") (pintype "power_in"))
      (node (ref "D165") (pin "2") (pinfunction "2_2") (pintype "power_in"))
      (node (ref "D166") (pin "2") (pinfunction "2_2") (pintype "power_in"))
      (node (ref "D167") (pin "2") (pinfunction "2_2") (pintype "power_in"))
      (node (ref "D168") (pin "2") (pinfunction "2_2") (pintype "power_in"))
      (node (ref "D169") (pin "2") (pinfunction "2_2") (pintype "power_in"))
      (node (ref "D170") (pin "2") (pinfunction "2_2") (pintype "power_in"))
      (node (ref "D171") (pin "2") (pinfunction "2_2") (pintype "power_in"))
    )
    (net (code "32") (name "Net-(D10-Pad1)") (class "Default")
      (node (ref "D10") (pin "1") (pinfunction "1_1") (pintype "power_in"))
      (node (ref "D106") (pin "1") (pinfunction "1_1") (pintype "power_in"))
      (node (ref "D130") (pin "1") (pinfunction "1_1") (pintype "power_in"))
      (node (ref "D154") (pin "1") (pinfunction "1_1") (pintype "power_in"))
      (node (ref "D34") (pin "1") (pinfunction "1_1") (pintype "power_in"))
      (node (ref "D58") (pin "1") (pinfunction "1_1") (pintype "power_in"))
      (node (ref "D82") (pin "1") (pinfunction "1_1") (pintype "power_in"))
      (node (ref "R15") (pin "1") (pinfunction "1_1") (pintype "passive"))
    )
    (net (code "33") (name "Net-(D100-Pad1)") (class "Default")
      (node (ref "D100") (pin "1") (pinfunction "1_1") (pintype "power_in"))
      (node (ref "D124") (pin "1") (pinfunction "1_1") (pintype "power_in"))
      (node (ref "D148") (pin "1") (pinfunction "1_1") (pintype "power_in"))
      (node (ref "D28") (pin "1") (pinfunction "1_1") (pintype "power_in"))
      (node (ref "D4") (pin "1") (pinfunction "1_1") (pintype "power_in"))
      (node (ref "D52") (pin "1") (pinfunction "1_1") (pintype "power_in"))
      (node (ref "D76") (pin "1") (pinfunction "1_1") (pintype "power_in"))
      (node (ref "R9") (pin "1") (pinfunction "1_1") (pintype "passive"))
    )
    (net (code "34") (name "Net-(D101-Pad1)") (class "Default")
      (node (ref "D101") (pin "1") (pinfunction "1_1") (pintype "power_in"))
      (node (ref "D125") (pin "1") (pinfunction "1_1") (pintype "power_in"))
      (node (ref "D149") (pin "1") (pinfunction "1_1") (pintype "power_in"))
      (node (ref "D29") (pin "1") (pinfunction "1_1") (pintype "power_in"))
      (node (ref "D5") (pin "1") (pinfunction "1_1") (pintype "power_in"))
      (node (ref "D53") (pin "1") (pinfunction "1_1") (pintype "power_in"))
      (node (ref "D77") (pin "1") (pinfunction "1_1") (pintype "power_in"))
      (node (ref "R10") (pin "1") (pinfunction "1_1") (pintype "passive"))
    )
    (net (code "35") (name "Net-(D102-Pad1)") (class "Default")
      (node (ref "D102") (pin "1") (pinfunction "1_1") (pintype "power_in"))
      (node (ref "D126") (pin "1") (pinfunction "1_1") (pintype "power_in"))
      (node (ref "D150") (pin "1") (pinfunction "1_1") (pintype "power_in"))
      (node (ref "D30") (pin "1") (pinfunction "1_1") (pintype "power_in"))
      (node (ref "D54") (pin "1") (pinfunction "1_1") (pintype "power_in"))
      (node (ref "D6") (pin "1") (pinfunction "1_1") (pintype "power_in"))
      (node (ref "D78") (pin "1") (pinfunction "1_1") (pintype "power_in"))
      (node (ref "R11") (pin "1") (pinfunction "1_1") (pintype "passive"))
    )
    (net (code "36") (name "Net-(D103-Pad1)") (class "Default")
      (node (ref "D103") (pin "1") (pinfunction "1_1") (pintype "power_in"))
      (node (ref "D127") (pin "1") (pinfunction "1_1") (pintype "power_in"))
      (node (ref "D151") (pin "1") (pinfunction "1_1") (pintype "power_in"))
      (node (ref "D31") (pin "1") (pinfunction "1_1") (pintype "power_in"))
      (node (ref "D55") (pin "1") (pinfunction "1_1") (pintype "power_in"))
      (node (ref "D7") (pin "1") (pinfunction "1_1") (pintype "power_in"))
      (node (ref "D79") (pin "1") (pinfunction "1_1") (pintype "power_in"))
      (node (ref "R12") (pin "1") (pinfunction "1_1") (pintype "passive"))
    )
    (net (code "37") (name "Net-(D104-Pad1)") (class "Default")
      (node (ref "D104") (pin "1") (pinfunction "1_1") (pintype "power_in"))
      (node (ref "D128") (pin "1") (pinfunction "1_1") (pintype "power_in"))
      (node (ref "D152") (pin "1") (pinfunction "1_1") (pintype "power_in"))
      (node (ref "D32") (pin "1") (pinfunction "1_1") (pintype "power_in"))
      (node (ref "D56") (pin "1") (pinfunction "1_1") (pintype "power_in"))
      (node (ref "D8") (pin "1") (pinfunction "1_1") (pintype "power_in"))
      (node (ref "D80") (pin "1") (pinfunction "1_1") (pintype "power_in"))
      (node (ref "R13") (pin "1") (pinfunction "1_1") (pintype "passive"))
    )
    (net (code "38") (name "Net-(D105-Pad1)") (class "Default")
      (node (ref "D105") (pin "1") (pinfunction "1_1") (pintype "power_in"))
      (node (ref "D129") (pin "1") (pinfunction "1_1") (pintype "power_in"))
      (node (ref "D153") (pin "1") (pinfunction "1_1") (pintype "power_in"))
      (node (ref "D33") (pin "1") (pinfunction "1_1") (pintype "power_in"))
      (node (ref "D57") (pin "1") (pinfunction "1_1") (pintype "power_in"))
      (node (ref "D81") (pin "1") (pinfunction "1_1") (pintype "power_in"))
      (node (ref "D9") (pin "1") (pinfunction "1_1") (pintype "power_in"))
      (node (ref "R14") (pin "1") (pinfunction "1_1") (pintype "passive"))
    )
    (net (code "39") (name "Net-(D107-Pad1)") (class "Default")
      (node (ref "D107") (pin "1") (pinfunction "1_1") (pintype "power_in"))
      (node (ref "D11") (pin "1") (pinfunction "1_1") (pintype "power_in"))
      (node (ref "D131") (pin "1") (pinfunction "1_1") (pintype "power_in"))
      (node (ref "D155") (pin "1") (pinfunction "1_1") (pintype "power_in"))
      (node (ref "D35") (pin "1") (pinfunction "1_1") (pintype "power_in"))
      (node (ref "D59") (pin "1") (pinfunction "1_1") (pintype "power_in"))
      (node (ref "D83") (pin "1") (pinfunction "1_1") (pintype "power_in"))
      (node (ref "R16") (pin "1") (pinfunction "1_1") (pintype "passive"))
    )
    (net (code "40") (name "Net-(D108-Pad1)") (class "Default")
      (node (ref "D108") (pin "1") (pinfunction "1_1") (pintype "power_in"))
      (node (ref "D12") (pin "1") (pinfunction "1_1") (pintype "power_in"))
      (node (ref "D132") (pin "1") (pinfunction "1_1") (pintype "power_in"))
      (node (ref "D156") (pin "1") (pinfunction "1_1") (pintype "power_in"))
      (node (ref "D36") (pin "1") (pinfunction "1_1") (pintype "power_in"))
      (node (ref "D60") (pin "1") (pinfunction "1_1") (pintype "power_in"))
      (node (ref "D84") (pin "1") (pinfunction "1_1") (pintype "power_in"))
      (node (ref "R17") (pin "1") (pinfunction "1_1") (pintype "passive"))
    )
    (net (code "41") (name "Net-(D109-Pad1)") (class "Default")
      (node (ref "D109") (pin "1") (pinfunction "1_1") (pintype "power_in"))
      (node (ref "D13") (pin "1") (pinfunction "1_1") (pintype "power_in"))
      (node (ref "D133") (pin "1") (pinfunction "1_1") (pintype "power_in"))
      (node (ref "D157") (pin "1") (pinfunction "1_1") (pintype "power_in"))
      (node (ref "D37") (pin "1") (pinfunction "1_1") (pintype "power_in"))
      (node (ref "D61") (pin "1") (pinfunction "1_1") (pintype "power_in"))
      (node (ref "D85") (pin "1") (pinfunction "1_1") (pintype "power_in"))
      (node (ref "R18") (pin "1") (pinfunction "1_1") (pintype "passive"))
    )
    (net (code "42") (name "Net-(D110-Pad1)") (class "Default")
      (node (ref "D110") (pin "1") (pinfunction "1_1") (pintype "power_in"))
      (node (ref "D134") (pin "1") (pinfunction "1_1") (pintype "power_in"))
      (node (ref "D14") (pin "1") (pinfunction "1_1") (pintype "power_in"))
      (node (ref "D158") (pin "1") (pinfunction "1_1") (pintype "power_in"))
      (node (ref "D38") (pin "1") (pinfunction "1_1") (pintype "power_in"))
      (node (ref "D62") (pin "1") (pinfunction "1_1") (pintype "power_in"))
      (node (ref "D86") (pin "1") (pinfunction "1_1") (pintype "power_in"))
      (node (ref "R19") (pin "1") (pinfunction "1_1") (pintype "passive"))
    )
    (net (code "43") (name "Net-(D111-Pad1)") (class "Default")
      (node (ref "D111") (pin "1") (pinfunction "1_1") (pintype "power_in"))
      (node (ref "D135") (pin "1") (pinfunction "1_1") (pintype "power_in"))
      (node (ref "D15") (pin "1") (pinfunction "1_1") (pintype "power_in"))
      (node (ref "D159") (pin "1") (pinfunction "1_1") (pintype "power_in"))
      (node (ref "D39") (pin "1") (pinfunction "1_1") (pintype "power_in"))
      (node (ref "D63") (pin "1") (pinfunction "1_1") (pintype "power_in"))
      (node (ref "D87") (pin "1") (pinfunction "1_1") (pintype "power_in"))
      (node (ref "R20") (pin "1") (pinfunction "1_1") (pintype "passive"))
    )
    (net (code "44") (name "Net-(D112-Pad1)") (class "Default")
      (node (ref "D112") (pin "1") (pinfunction "1_1") (pintype "power_in"))
      (node (ref "D136") (pin "1") (pinfunction "1_1") (pintype "power_in"))
      (node (ref "D16") (pin "1") (pinfunction "1_1") (pintype "power_in"))
      (node (ref "D160") (pin "1") (pinfunction "1_1") (pintype "power_in"))
      (node (ref "D40") (pin "1") (pinfunction "1_1") (pintype "power_in"))
      (node (ref "D64") (pin "1") (pinfunction "1_1") (pintype "power_in"))
      (node (ref "D88") (pin "1") (pinfunction "1_1") (pintype "power_in"))
      (node (ref "R21") (pin "1") (pinfunction "1_1") (pintype "passive"))
    )
    (net (code "45") (name "Net-(D113-Pad1)") (class "Default")
      (node (ref "D113") (pin "1") (pinfunction "1_1") (pintype "power_in"))
      (node (ref "D137") (pin "1") (pinfunction "1_1") (pintype "power_in"))
      (node (ref "D161") (pin "1") (pinfunction "1_1") (pintype "power_in"))
      (node (ref "D17") (pin "1") (pinfunction "1_1") (pintype "power_in"))
      (node (ref "D41") (pin "1") (pinfunction "1_1") (pintype "power_in"))
      (node (ref "D65") (pin "1") (pinfunction "1_1") (pintype "power_in"))
      (node (ref "D89") (pin "1") (pinfunction "1_1") (pintype "power_in"))
      (node (ref "R22") (pin "1") (pinfunction "1_1") (pintype "passive"))
    )
    (net (code "46") (name "Net-(D114-Pad1)") (class "Default")
      (node (ref "D114") (pin "1") (pinfunction "1_1") (pintype "power_in"))
      (node (ref "D138") (pin "1") (pinfunction "1_1") (pintype "power_in"))
      (node (ref "D162") (pin "1") (pinfunction "1_1") (pintype "power_in"))
      (node (ref "D18") (pin "1") (pinfunction "1_1") (pintype "power_in"))
      (node (ref "D42") (pin "1") (pinfunction "1_1") (pintype "power_in"))
      (node (ref "D66") (pin "1") (pinfunction "1_1") (pintype "power_in"))
      (node (ref "D90") (pin "1") (pinfunction "1_1") (pintype "power_in"))
      (node (ref "R23") (pin "1") (pinfunction "1_1") (pintype "passive"))
    )
    (net (code "47") (name "Net-(D115-Pad1)") (class "Default")
      (node (ref "D115") (pin "1") (pinfunction "1_1") (pintype "power_in"))
      (node (ref "D139") (pin "1") (pinfunction "1_1") (pintype "power_in"))
      (node (ref "D163") (pin "1") (pinfunction "1_1") (pintype "power_in"))
      (node (ref "D19") (pin "1") (pinfunction "1_1") (pintype "power_in"))
      (node (ref "D43") (pin "1") (pinfunction "1_1") (pintype "power_in"))
      (node (ref "D67") (pin "1") (pinfunction "1_1") (pintype "power_in"))
      (node (ref "D91") (pin "1") (pinfunction "1_1") (pintype "power_in"))
      (node (ref "R24") (pin "1") (pinfunction "1_1") (pintype "passive"))
    )
    (net (code "48") (name "Net-(D116-Pad1)") (class "Default")
      (node (ref "D116") (pin "1") (pinfunction "1_1") (pintype "power_in"))
      (node (ref "D140") (pin "1") (pinfunction "1_1") (pintype "power_in"))
      (node (ref "D164") (pin "1") (pinfunction "1_1") (pintype "power_in"))
      (node (ref "D20") (pin "1") (pinfunction "1_1") (pintype "power_in"))
      (node (ref "D44") (pin "1") (pinfunction "1_1") (pintype "power_in"))
      (node (ref "D68") (pin "1") (pinfunction "1_1") (pintype "power_in"))
      (node (ref "D92") (pin "1") (pinfunction "1_1") (pintype "power_in"))
      (node (ref "R25") (pin "1") (pinfunction "1_1") (pintype "passive"))
    )
    (net (code "49") (name "Net-(D117-Pad1)") (class "Default")
      (node (ref "D117") (pin "1") (pinfunction "1_1") (pintype "power_in"))
      (node (ref "D141") (pin "1") (pinfunction "1_1") (pintype "power_in"))
      (node (ref "D165") (pin "1") (pinfunction "1_1") (pintype "power_in"))
      (node (ref "D21") (pin "1") (pinfunction "1_1") (pintype "power_in"))
      (node (ref "D45") (pin "1") (pinfunction "1_1") (pintype "power_in"))
      (node (ref "D69") (pin "1") (pinfunction "1_1") (pintype "power_in"))
      (node (ref "D93") (pin "1") (pinfunction "1_1") (pintype "power_in"))
      (node (ref "R26") (pin "1") (pinfunction "1_1") (pintype "passive"))
    )
    (net (code "50") (name "Net-(D118-Pad1)") (class "Default")
      (node (ref "D118") (pin "1") (pinfunction "1_1") (pintype "power_in"))
      (node (ref "D142") (pin "1") (pinfunction "1_1") (pintype "power_in"))
      (node (ref "D166") (pin "1") (pinfunction "1_1") (pintype "power_in"))
      (node (ref "D22") (pin "1") (pinfunction "1_1") (pintype "power_in"))
      (node (ref "D46") (pin "1") (pinfunction "1_1") (pintype "power_in"))
      (node (ref "D70") (pin "1") (pinfunction "1_1") (pintype "power_in"))
      (node (ref "D94") (pin "1") (pinfunction "1_1") (pintype "power_in"))
      (node (ref "R27") (pin "1") (pinfunction "1_1") (pintype "passive"))
    )
    (net (code "51") (name "Net-(D119-Pad1)") (class "Default")
      (node (ref "D119") (pin "1") (pinfunction "1_1") (pintype "power_in"))
      (node (ref "D143") (pin "1") (pinfunction "1_1") (pintype "power_in"))
      (node (ref "D167") (pin "1") (pinfunction "1_1") (pintype "power_in"))
      (node (ref "D23") (pin "1") (pinfunction "1_1") (pintype "power_in"))
      (node (ref "D47") (pin "1") (pinfunction "1_1") (pintype "power_in"))
      (node (ref "D71") (pin "1") (pinfunction "1_1") (pintype "power_in"))
      (node (ref "D95") (pin "1") (pinfunction "1_1") (pintype "power_in"))
      (node (ref "R28") (pin "1") (pinfunction "1_1") (pintype "passive"))
    )
    (net (code "52") (name "Net-(D120-Pad1)") (class "Default")
      (node (ref "D120") (pin "1") (pinfunction "1_1") (pintype "power_in"))
      (node (ref "D144") (pin "1") (pinfunction "1_1") (pintype "power_in"))
      (node (ref "D168") (pin "1") (pinfunction "1_1") (pintype "power_in"))
      (node (ref "D24") (pin "1") (pinfunction "1_1") (pintype "power_in"))
      (node (ref "D48") (pin "1") (pinfunction "1_1") (pintype "power_in"))
      (node (ref "D72") (pin "1") (pinfunction "1_1") (pintype "power_in"))
      (node (ref "D96") (pin "1") (pinfunction "1_1") (pintype "power_in"))
      (node (ref "R29") (pin "1") (pinfunction "1_1") (pintype "passive"))
    )
    (net (code "53") (name "Net-(D121-Pad1)") (class "Default")
      (node (ref "D121") (pin "1") (pinfunction "1_1") (pintype "power_in"))
      (node (ref "D145") (pin "1") (pinfunction "1_1") (pintype "power_in"))
      (node (ref "D169") (pin "1") (pinfunction "1_1") (pintype "power_in"))
      (node (ref "D25") (pin "1") (pinfunction "1_1") (pintype "power_in"))
      (node (ref "D49") (pin "1") (pinfunction "1_1") (pintype "power_in"))
      (node (ref "D73") (pin "1") (pinfunction "1_1") (pintype "power_in"))
      (node (ref "D97") (pin "1") (pinfunction "1_1") (pintype "power_in"))
      (node (ref "R30") (pin "1") (pinfunction "1_1") (pintype "passive"))
    )
    (net (code "54") (name "Net-(D122-Pad1)") (class "Default")
      (node (ref "D122") (pin "1") (pinfunction "1_1") (pintype "power_in"))
      (node (ref "D146") (pin "1") (pinfunction "1_1") (pintype "power_in"))
      (node (ref "D170") (pin "1") (pinfunction "1_1") (pintype "power_in"))
      (node (ref "D26") (pin "1") (pinfunction "1_1") (pintype "power_in"))
      (node (ref "D50") (pin "1") (pinfunction "1_1") (pintype "power_in"))
      (node (ref "D74") (pin "1") (pinfunction "1_1") (pintype "power_in"))
      (node (ref "D98") (pin "1") (pinfunction "1_1") (pintype "power_in"))
      (node (ref "R31") (pin "1") (pinfunction "1_1") (pintype "passive"))
    )
    (net (code "55") (name "Net-(D123-Pad1)") (class "Default")
      (node (ref "D123") (pin "1") (pinfunction "1_1") (pintype "power_in"))
      (node (ref "D147") (pin "1") (pinfunction "1_1") (pintype "power_in"))
      (node (ref "D171") (pin "1") (pinfunction "1_1") (pintype "power_in"))
      (node (ref "D27") (pin "1") (pinfunction "1_1") (pintype "power_in"))
      (node (ref "D51") (pin "1") (pinfunction "1_1") (pintype "power_in"))
      (node (ref "D75") (pin "1") (pinfunction "1_1") (pintype "power_in"))
      (node (ref "D99") (pin "1") (pinfunction "1_1") (pintype "power_in"))
      (node (ref "R32") (pin "1") (pinfunction "1_1") (pintype "passive"))
    )
  )
)
